# sha2017_rev1_0_0.net
KiCad netlist of a schematic drawn in EAGLE
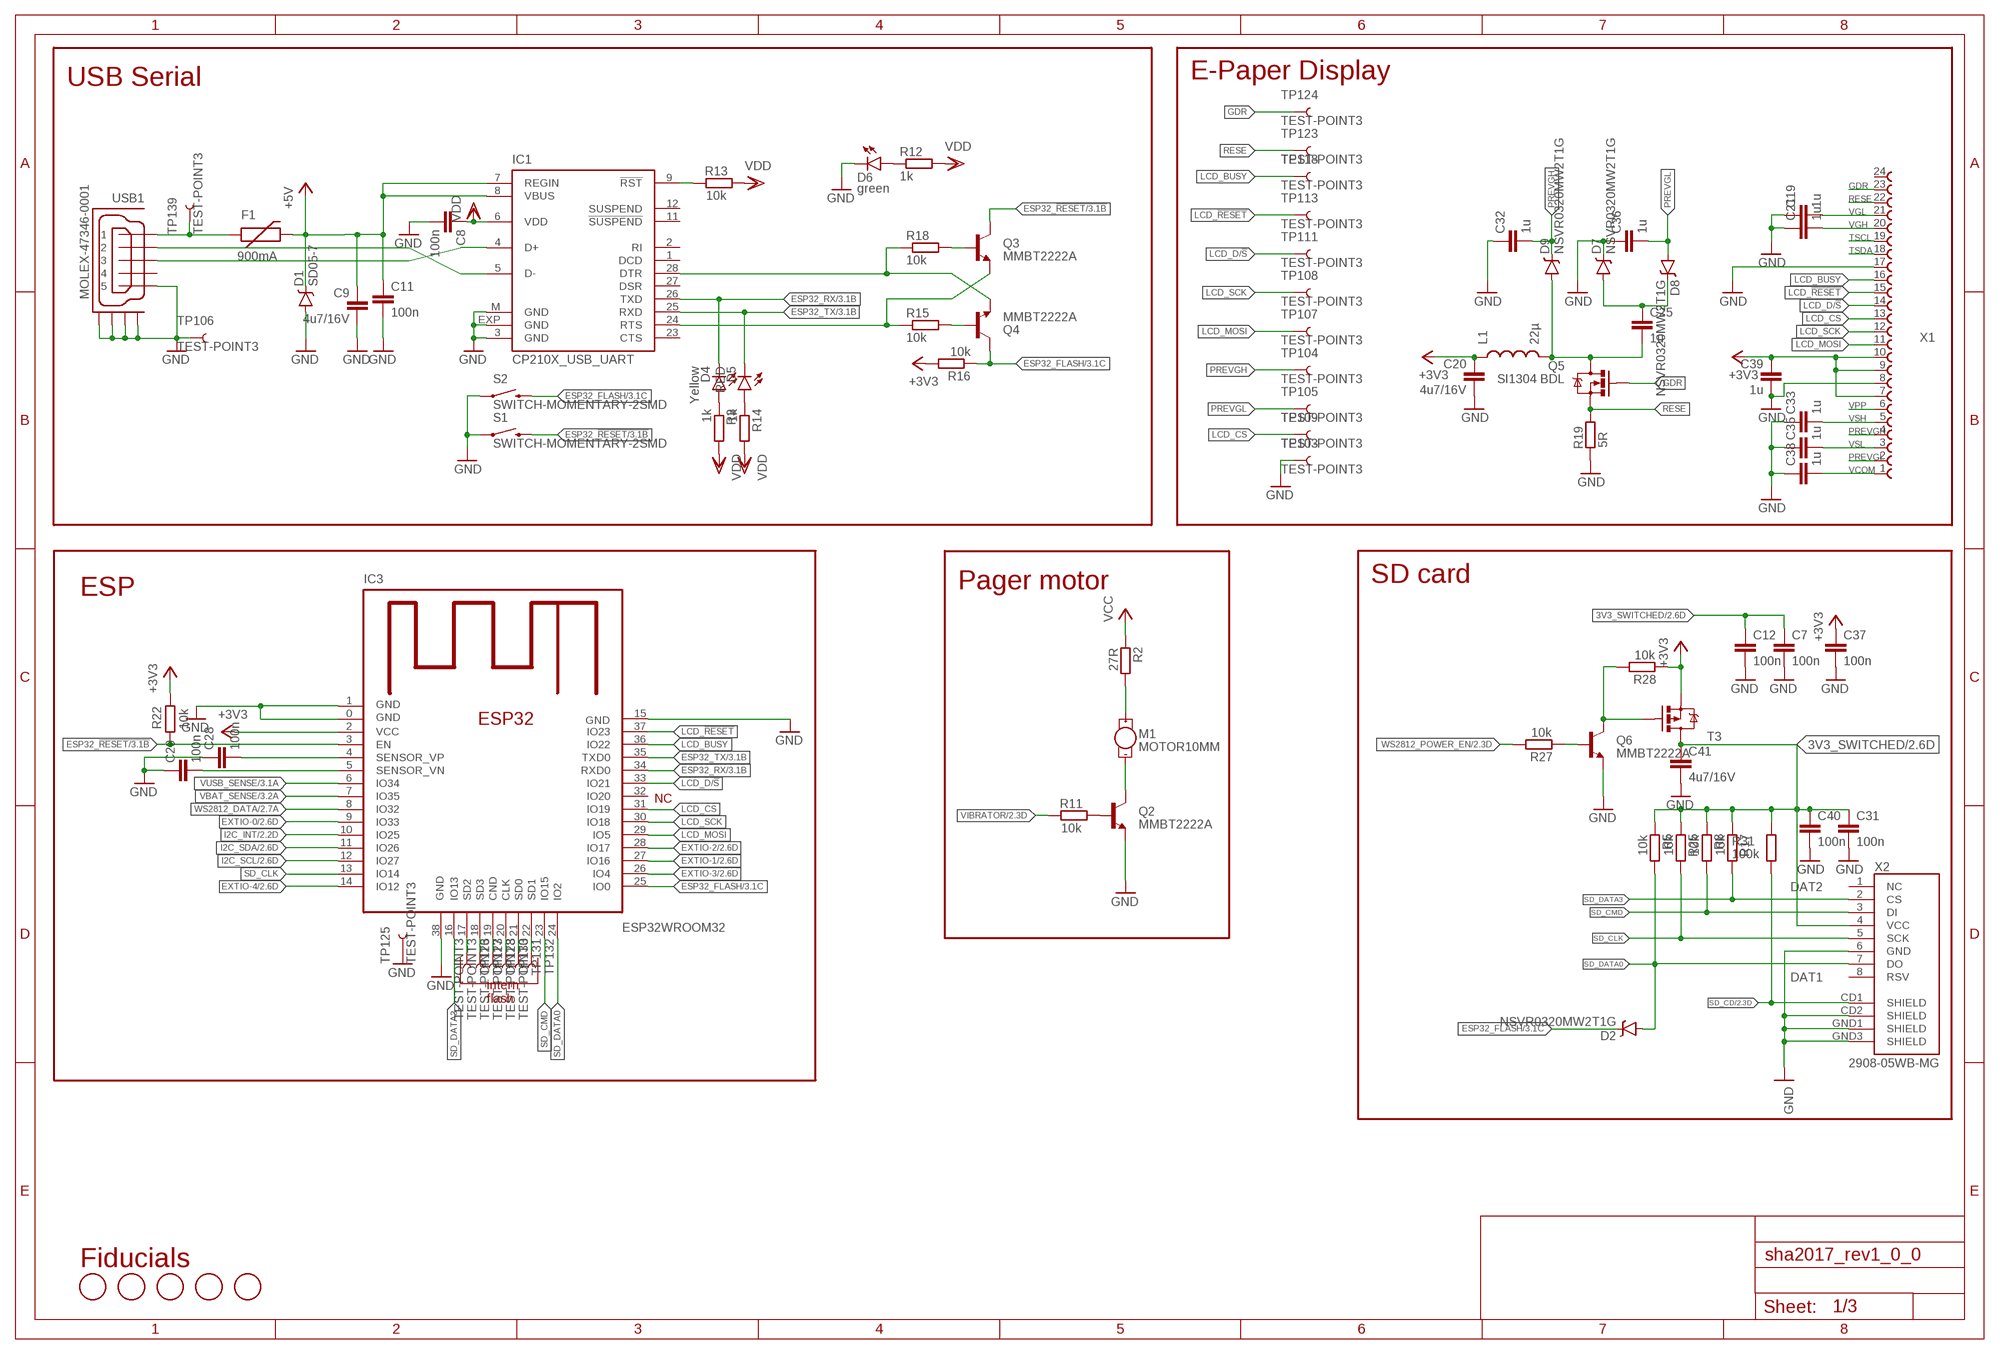
[diagram p0: schematic, sheet 1]
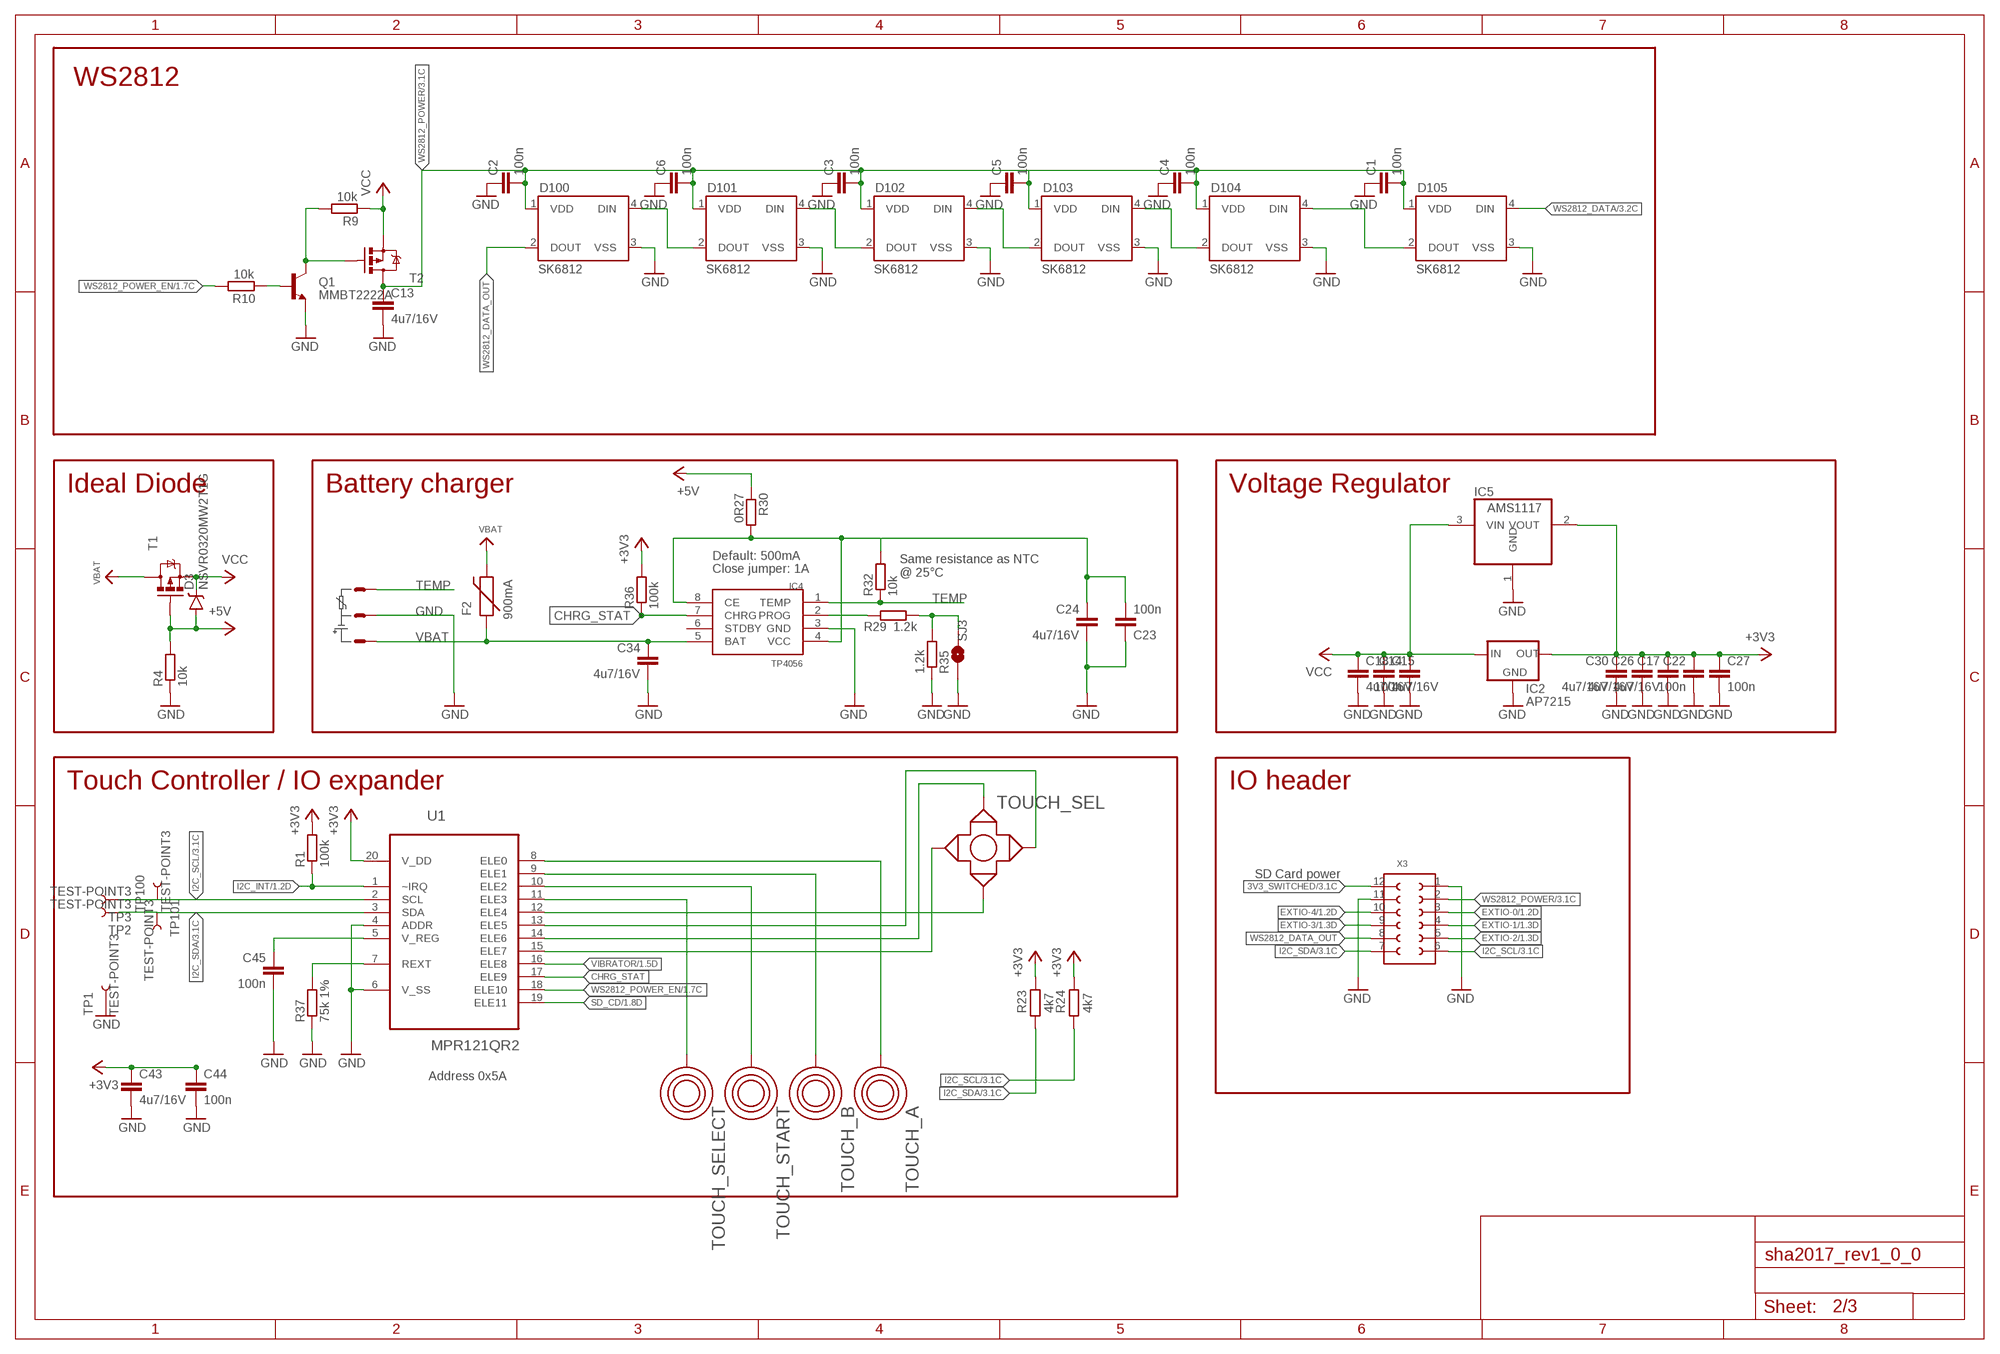
[diagram p1: schematic, sheet 2]
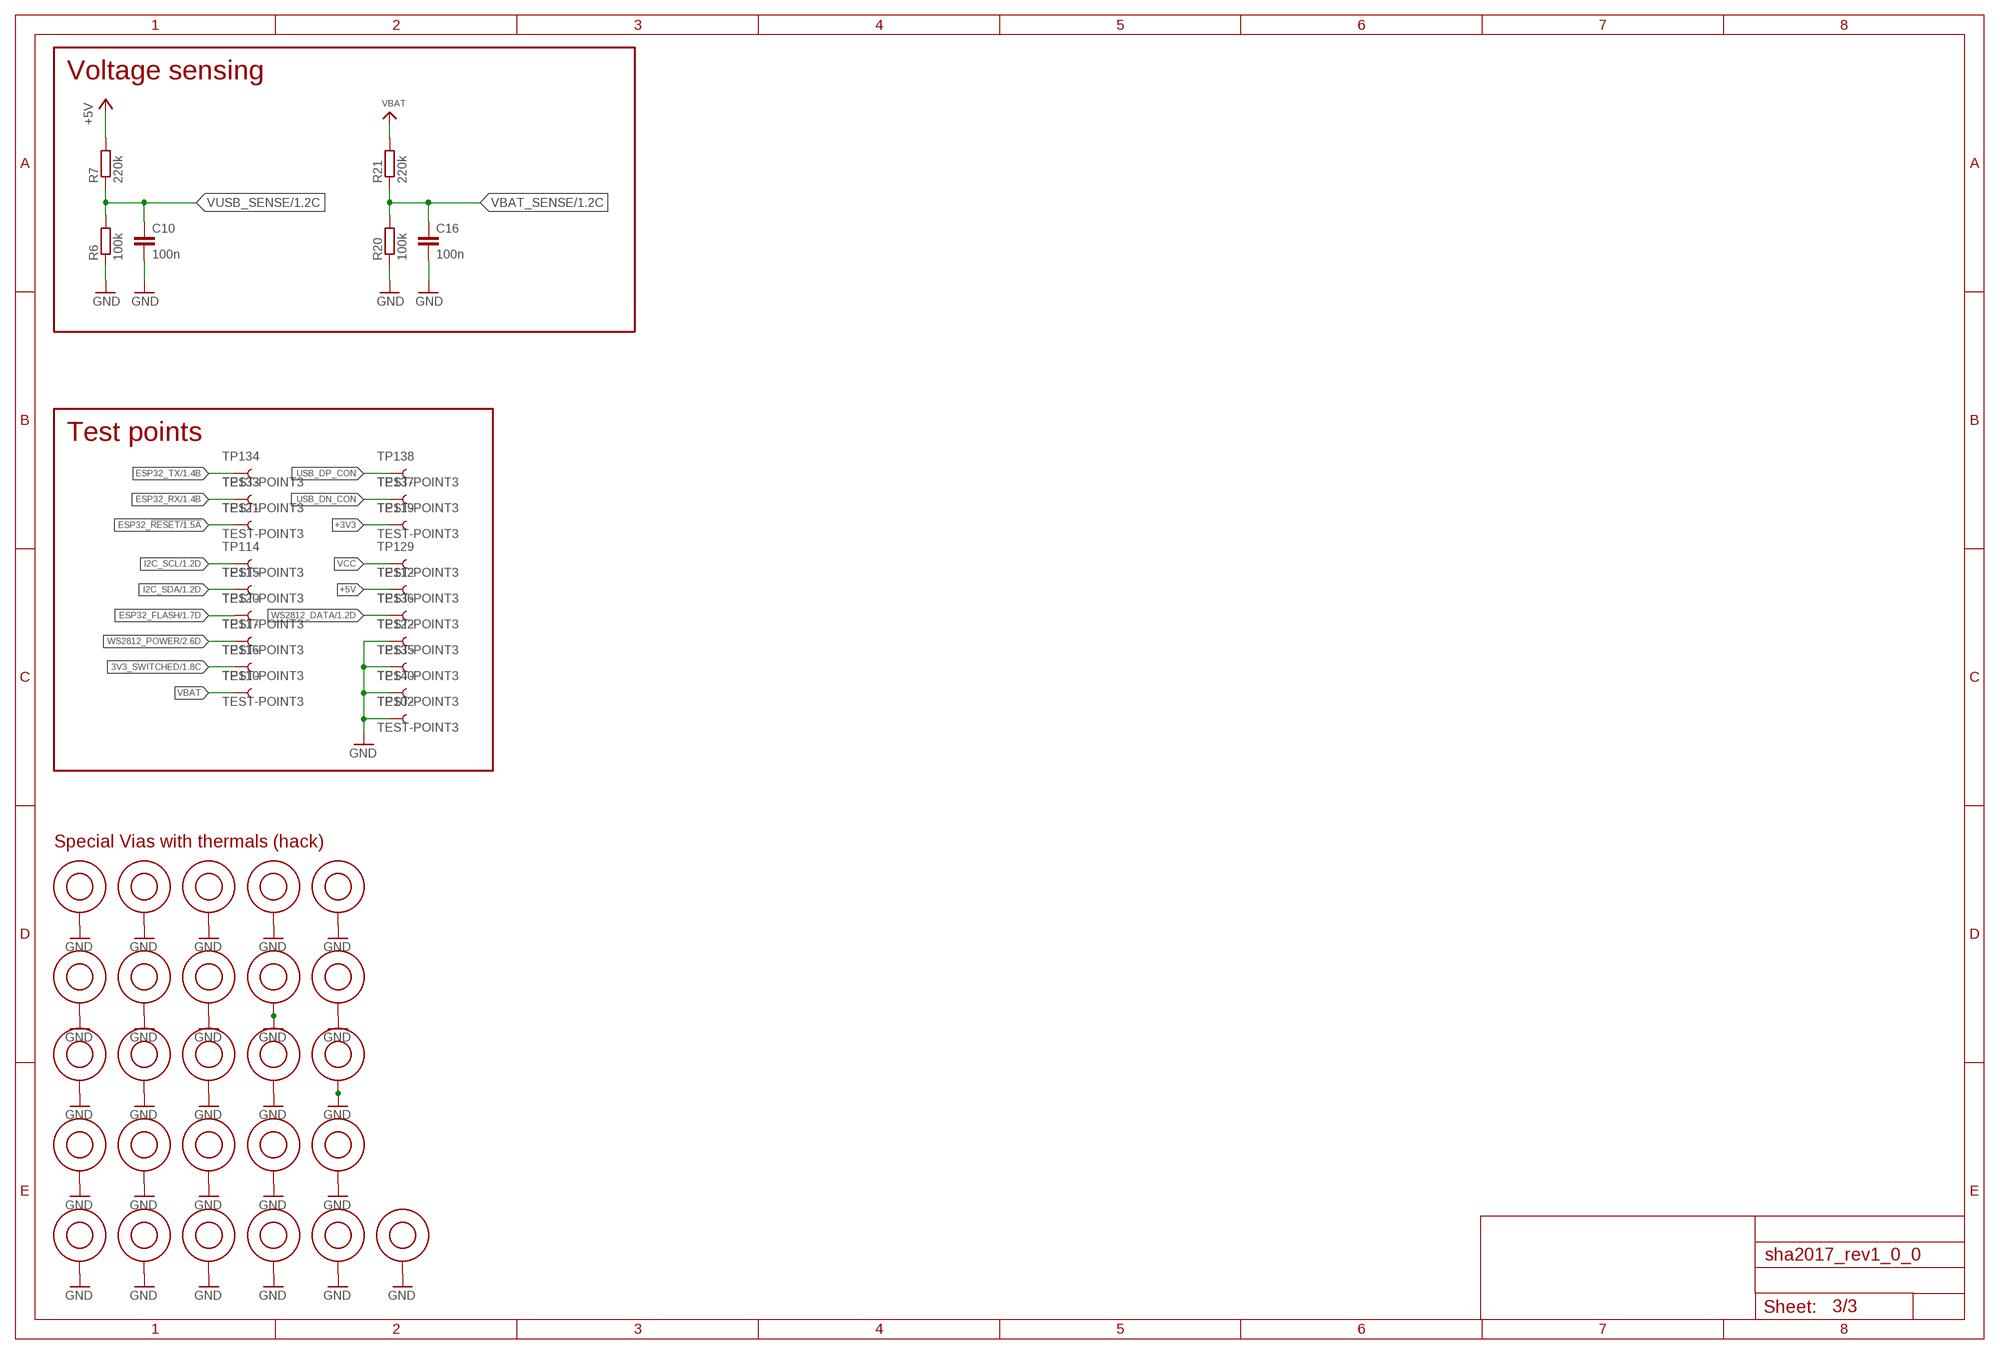
[diagram p2: schematic, sheet 3]

(export (version "E")
  (design (tool "Eeschema 10.0.6"))
  (components
    (comp (ref "C1")
      (value "100n")
      (footprint "eagle-import:C0603-DASHES")
      (fields (field (name "PARTNO") "GRM188R71H104KA93D"))
      (libsource (lib "eagle-import") (part "C0603-DASHES"))
    )
    (comp (ref "C2")
      (value "100n")
      (footprint "eagle-import:C0603-DASHES")
      (fields (field (name "PARTNO") "GRM188R71H104KA93D"))
      (libsource (lib "eagle-import") (part "C0603-DASHES"))
    )
    (comp (ref "C3")
      (value "100n")
      (footprint "eagle-import:C0603-DASHES")
      (fields (field (name "PARTNO") "GRM188R71H104KA93D"))
      (libsource (lib "eagle-import") (part "C0603-DASHES"))
    )
    (comp (ref "C4")
      (value "100n")
      (footprint "eagle-import:C0603-DASHES")
      (fields (field (name "PARTNO") "GRM188R71H104KA93D"))
      (libsource (lib "eagle-import") (part "C0603-DASHES"))
    )
    (comp (ref "C5")
      (value "100n")
      (footprint "eagle-import:C0603-DASHES")
      (fields (field (name "PARTNO") "GRM188R71H104KA93D"))
      (libsource (lib "eagle-import") (part "C0603-DASHES"))
    )
    (comp (ref "C6")
      (value "100n")
      (footprint "eagle-import:C0603-DASHES")
      (fields (field (name "PARTNO") "GRM188R71H104KA93D"))
      (libsource (lib "eagle-import") (part "C0603-DASHES"))
    )
    (comp (ref "C13")
      (value "4u7/16V")
      (footprint "eagle-import:C0805")
      (fields (field (name "PARTNO") "GRM21BR61C475KA88K"))
      (libsource (lib "eagle-import") (part "C-EUC0805"))
    )
    (comp (ref "C14")
      (value "100n")
      (footprint "eagle-import:C0603-DASHES")
      (fields (field (name "PARTNO") "GRM188R71H104KA93D"))
      (libsource (lib "eagle-import") (part "C0603-DASHES"))
    )
    (comp (ref "C15")
      (value "4u7/16V")
      (footprint "eagle-import:C0805")
      (fields (field (name "PARTNO") "GRM21BR61C475KA88K"))
      (libsource (lib "eagle-import") (part "C-EUC0805"))
    )
    (comp (ref "C17")
      (value "4u7/16V")
      (footprint "eagle-import:C0805")
      (fields (field (name "PARTNO") "GRM21BR61C475KA88K"))
      (libsource (lib "eagle-import") (part "C-EUC0805"))
    )
    (comp (ref "C18")
      (value "4u7/16V")
      (footprint "eagle-import:C0805")
      (fields (field (name "PARTNO") "GRM21BR61C475KA88K"))
      (libsource (lib "eagle-import") (part "C-EUC0805"))
    )
    (comp (ref "C22")
      (value "100n")
      (footprint "eagle-import:C0603-DASHES")
      (fields (field (name "PARTNO") "GRM188R71H104KA93D"))
      (libsource (lib "eagle-import") (part "C0603-DASHES"))
    )
    (comp (ref "C23")
      (value "100n")
      (footprint "eagle-import:C0603-DASHES")
      (fields (field (name "PARTNO") "GRM188R71H104KA93D"))
      (libsource (lib "eagle-import") (part "C0603-DASHES"))
    )
    (comp (ref "C24")
      (value "4u7/16V")
      (footprint "eagle-import:C0805")
      (fields (field (name "PARTNO") "GRM21BR61C475KA88K"))
      (libsource (lib "eagle-import") (part "C-EUC0805"))
    )
    (comp (ref "C26")
      (value "4u7/16V")
      (footprint "eagle-import:C0805")
      (fields (field (name "PARTNO") "GRM21BR61C475KA88K"))
      (libsource (lib "eagle-import") (part "C-EUC0805"))
    )
    (comp (ref "C27")
      (value "100n")
      (footprint "eagle-import:C0603-DASHES")
      (fields (field (name "PARTNO") "GRM188R71H104KA93D"))
      (libsource (lib "eagle-import") (part "C0603-DASHES"))
    )
    (comp (ref "C30")
      (value "4u7/16V")
      (footprint "eagle-import:C0805")
      (fields (field (name "PARTNO") "GRM21BR61C475KA88K"))
      (libsource (lib "eagle-import") (part "C-EUC0805"))
    )
    (comp (ref "C34")
      (value "4u7/16V")
      (footprint "eagle-import:C0805")
      (fields (field (name "PARTNO") "GRM21BR61C475KA88K"))
      (libsource (lib "eagle-import") (part "C-EUC0805"))
    )
    (comp (ref "C43")
      (value "4u7/16V")
      (footprint "eagle-import:C0805")
      (fields (field (name "PARTNO") "GRM21BR61C475KA88K"))
      (libsource (lib "eagle-import") (part "C-EUC0805"))
    )
    (comp (ref "C44")
      (value "100n")
      (footprint "eagle-import:C0603-DASHES")
      (fields (field (name "PARTNO") "GRM188R71H104KA93D"))
      (libsource (lib "eagle-import") (part "C0603-DASHES"))
    )
    (comp (ref "C45")
      (value "100n")
      (footprint "eagle-import:C0603-DASHES")
      (fields (field (name "PARTNO") "GRM188R71H104KA93D"))
      (libsource (lib "eagle-import") (part "C0603-DASHES"))
    )
    (comp (ref "D3")
      (value "NSVR0320MW2T1G")
      (footprint "eagle-import:SOD-323")
      (fields (field (name "PARTNO") "BAT20JFILM"))
      (libsource (lib "eagle-import") (part "BAT20JFILM"))
    )
    (comp (ref "D100")
      (value "SK6812")
      (footprint "eagle-import:WS2812B")
      (libsource (lib "eagle-import") (part "WS2812B"))
    )
    (comp (ref "D101")
      (value "SK6812")
      (footprint "eagle-import:WS2812B")
      (libsource (lib "eagle-import") (part "WS2812B"))
    )
    (comp (ref "D102")
      (value "SK6812")
      (footprint "eagle-import:WS2812B")
      (libsource (lib "eagle-import") (part "WS2812B"))
    )
    (comp (ref "D103")
      (value "SK6812")
      (footprint "eagle-import:WS2812B")
      (libsource (lib "eagle-import") (part "WS2812B"))
    )
    (comp (ref "D104")
      (value "SK6812")
      (footprint "eagle-import:WS2812B")
      (libsource (lib "eagle-import") (part "WS2812B"))
    )
    (comp (ref "D105")
      (value "SK6812")
      (footprint "eagle-import:WS2812B")
      (libsource (lib "eagle-import") (part "WS2812B"))
    )
    (comp (ref "F2")
      (value "900mA")
      (footprint "eagle-import:PTC-1206")
      (libsource (lib "eagle-import") (part "PTCSMD"))
    )
    (comp (ref "IC2")
      (value "AP7215")
      (footprint "eagle-import:SOT89")
      (fields (field (name "PARTNO") "AP7215-33YG-13"))
      (libsource (lib "eagle-import") (part "AP7215"))
    )
    (comp (ref "IC4")
      (value "TP4056")
      (footprint "eagle-import:SOP-8")
      (libsource (lib "eagle-import") (part "TP4056"))
    )
    (comp (ref "IC5")
      (value "AMS1117")
      (footprint "eagle-import:SOT223")
      (fields (field (name "MPN") "REG1117"))
      (libsource (lib "eagle-import") (part "REG1117"))
    )
    (comp (ref "Q1")
      (value "MMBT2222A")
      (footprint "eagle-import:SOT23-3")
      (fields (field (name "PARTNO") "BC817-25,215"))
      (libsource (lib "eagle-import") (part "TRANSISTOR_NPNMMBT2222A"))
    )
    (comp (ref "R1")
      (value "100k")
      (footprint "eagle-import:R0603-DASHES")
      (fields (field (name "PARTNO") "ERJ-3GEYJ104V"))
      (libsource (lib "eagle-import") (part "sha2017_rev0_1_0_dev_R0603-DASHES"))
    )
    (comp (ref "R4")
      (value "10k")
      (footprint "eagle-import:R0603-DASHES")
      (fields (field (name "PARTNO") "ERJ-3GEYJ103V"))
      (libsource (lib "eagle-import") (part "sha2017_rev0_1_0_dev_R0603-DASHES"))
    )
    (comp (ref "R9")
      (value "10k")
      (footprint "eagle-import:R0603-DASHES")
      (fields (field (name "PARTNO") "ERJ-3GEYJ103V"))
      (libsource (lib "eagle-import") (part "R0603-DASHES"))
    )
    (comp (ref "R10")
      (value "10k")
      (footprint "eagle-import:R0603-DASHES")
      (fields (field (name "PARTNO") "ERJ-3GEYJ103V"))
      (libsource (lib "eagle-import") (part "R0603-DASHES"))
    )
    (comp (ref "R23")
      (value "4k7")
      (footprint "eagle-import:R0603-DASHES")
      (fields (field (name "PARTNO") "ERJ-3GEYJ103V"))
      (libsource (lib "eagle-import") (part "sha2017_rev0_1_0_dev_R0603-DASHES"))
    )
    (comp (ref "R24")
      (value "4k7")
      (footprint "eagle-import:R0603-DASHES")
      (fields (field (name "PARTNO") "ERJ-3GEYJ103V"))
      (libsource (lib "eagle-import") (part "sha2017_rev0_1_0_dev_R0603-DASHES"))
    )
    (comp (ref "R29")
      (value "1.2k")
      (footprint "eagle-import:R0603-DASHES")
      (fields (field (name "PARTNO") "ERJ-3GEYJ222V"))
      (libsource (lib "eagle-import") (part "sha2017_rev0_1_0_dev_R0603-DASHES"))
    )
    (comp (ref "R30")
      (value "0R27")
      (footprint "eagle-import:R1206")
      (fields (field (name "PARTNO") "ERJ-3GEYJ154V"))
      (libsource (lib "eagle-import") (part "R-EU_R1206"))
    )
    (comp (ref "R32")
      (value "10k")
      (footprint "eagle-import:R0603-DASHES")
      (fields (field (name "PARTNO") "ERJ-3GEYJ154V"))
      (libsource (lib "eagle-import") (part "sha2017_rev0_1_0_dev_R0603-DASHES"))
    )
    (comp (ref "R35")
      (value "1.2k")
      (footprint "eagle-import:R0603-DASHES")
      (fields (field (name "PARTNO") "ERJ-3GEYJ222V"))
      (libsource (lib "eagle-import") (part "sha2017_rev0_1_0_dev_R0603-DASHES"))
    )
    (comp (ref "R36")
      (value "100k")
      (footprint "eagle-import:R0603-DASHES")
      (fields (field (name "PARTNO") "ERJ-3GEYJ104V"))
      (libsource (lib "eagle-import") (part "sha2017_rev0_1_0_dev_R0603-DASHES"))
    )
    (comp (ref "R37")
      (value "75k 1%")
      (footprint "eagle-import:R0603-DASHES")
      (fields (field (name "PARTNO") "ERJ-3GEYJ104V"))
      (libsource (lib "eagle-import") (part "sha2017_rev0_1_0_dev_R0603-DASHES"))
    )
    (comp (ref "SJ3")
      (value "JUMPER-PAD-2-NOYES_SILK")
      (footprint "eagle-import:PAD-JUMPER-2-NO_YES_SILK")
      (fields (field (name "PARTNO") "NAP"))
      (libsource (lib "eagle-import") (part "JUMPER-PAD-2-NOYES_SILK"))
    )
    (comp (ref "T1")
      (value "MOSFET-PCHANNEL")
      (footprint "eagle-import:SOT23-3")
      (libsource (lib "eagle-import") (part "MOSFET-PCHANNEL"))
    )
    (comp (ref "T2")
      (value "MOSFET-PCHANNEL")
      (footprint "eagle-import:SOT23-3")
      (libsource (lib "eagle-import") (part "MOSFET-PCHANNEL"))
    )
    (comp (ref "TOUCH_A")
      (value "TOUCHROUND")
      (footprint "eagle-import:TOUCH_BUTTON")
      (fields (field (name "PARTNO") "NAP"))
      (libsource (lib "eagle-import") (part "TOUCHROUND"))
    )
    (comp (ref "TOUCH_B")
      (value "TOUCHROUND")
      (footprint "eagle-import:TOUCH_BUTTON")
      (fields (field (name "PARTNO") "NAP"))
      (libsource (lib "eagle-import") (part "TOUCHROUND"))
    )
    (comp (ref "TOUCH_SEL")
      (value "TOUCH_CROSS")
      (footprint "eagle-import:TOUCH_CROSS")
      (fields (field (name "PARTNO") "NAP"))
      (libsource (lib "eagle-import") (part "TOUCH_CROSS"))
    )
    (comp (ref "TOUCH_SELECT")
      (value "TOUCHSELECT")
      (footprint "eagle-import:TOUCH_SELECT")
      (libsource (lib "eagle-import") (part "TOUCHSELECT"))
    )
    (comp (ref "TOUCH_START")
      (value "TOUCHSELECT")
      (footprint "eagle-import:TOUCH_SELECT")
      (libsource (lib "eagle-import") (part "TOUCHSELECT"))
    )
    (comp (ref "TP1")
      (value "TEST-POINT3")
      (footprint "eagle-import:PAD.03X.03")
      (fields (field (name "PARTNO") "NAP"))
      (libsource (lib "eagle-import") (part "TEST-POINT3"))
    )
    (comp (ref "TP2")
      (value "TEST-POINT3")
      (footprint "eagle-import:PAD.03X.03")
      (fields (field (name "PARTNO") "NAP"))
      (libsource (lib "eagle-import") (part "TEST-POINT3"))
    )
    (comp (ref "TP3")
      (value "TEST-POINT3")
      (footprint "eagle-import:PAD.03X.03")
      (fields (field (name "PARTNO") "NAP"))
      (libsource (lib "eagle-import") (part "TEST-POINT3"))
    )
    (comp (ref "TP100")
      (value "TEST-POINT3")
      (footprint "eagle-import:PAD.03X.03")
      (fields (field (name "PARTNO") "NAP"))
      (libsource (lib "eagle-import") (part "TEST-POINT3"))
    )
    (comp (ref "TP101")
      (value "TEST-POINT3")
      (footprint "eagle-import:PAD.03X.03")
      (fields (field (name "PARTNO") "NAP"))
      (libsource (lib "eagle-import") (part "TEST-POINT3"))
    )
    (comp (ref "U1")
      (value "MPR121QR2")
      (footprint "eagle-import:QFN40P300X300X60-20N")
      (libsource (lib "eagle-import") (part "MPR121QR2"))
    )
    (comp (ref "X3")
      (value "610X12243021")
      (footprint "eagle-import:610X12243021")
      (fields (field (name "PARTNO") "517-153208-2020-TB"))
      (libsource (lib "eagle-import") (part "610X12243021"))
    )
    (comp (ref "X4")
      (value "JST-PH3")
      (footprint "eagle-import:JST-PH3")
      (libsource (lib "eagle-import") (part "JST-PH3"))
    )
    (comp (ref "$$U$1")
      (value "VIA")
      (footprint "eagle-import:VIA")
      (fields (field (name "PARTNO") "NAP"))
      (libsource (lib "eagle-import") (part "VIA"))
    )
    (comp (ref "$$U$2")
      (value "VIA")
      (footprint "eagle-import:VIA")
      (fields (field (name "PARTNO") "NAP"))
      (libsource (lib "eagle-import") (part "VIA"))
    )
    (comp (ref "$$U$3")
      (value "VIA")
      (footprint "eagle-import:VIA")
      (fields (field (name "PARTNO") "NAP"))
      (libsource (lib "eagle-import") (part "VIA"))
    )
    (comp (ref "$$U$4")
      (value "VIA")
      (footprint "eagle-import:VIA")
      (fields (field (name "PARTNO") "NAP"))
      (libsource (lib "eagle-import") (part "VIA"))
    )
    (comp (ref "$$U$5")
      (value "VIA")
      (footprint "eagle-import:VIA")
      (fields (field (name "PARTNO") "NAP"))
      (libsource (lib "eagle-import") (part "VIA"))
    )
    (comp (ref "$$U$6")
      (value "VIA")
      (footprint "eagle-import:VIA")
      (fields (field (name "PARTNO") "NAP"))
      (libsource (lib "eagle-import") (part "VIA"))
    )
    (comp (ref "$$U$7")
      (value "VIA")
      (footprint "eagle-import:VIA")
      (fields (field (name "PARTNO") "NAP"))
      (libsource (lib "eagle-import") (part "VIA"))
    )
    (comp (ref "$$U$8")
      (value "VIA")
      (footprint "eagle-import:VIA")
      (fields (field (name "PARTNO") "NAP"))
      (libsource (lib "eagle-import") (part "VIA"))
    )
    (comp (ref "$$U$9")
      (value "VIA")
      (footprint "eagle-import:VIA")
      (fields (field (name "PARTNO") "NAP"))
      (libsource (lib "eagle-import") (part "VIA"))
    )
    (comp (ref "C10")
      (value "100n")
      (footprint "eagle-import:C0603-DASHES")
      (fields (field (name "PARTNO") "GRM188R71H104KA93D"))
      (libsource (lib "eagle-import") (part "C0603-DASHES"))
    )
    (comp (ref "C16")
      (value "100n")
      (footprint "eagle-import:C0603-DASHES")
      (fields (field (name "PARTNO") "GRM188R71H104KA93D"))
      (libsource (lib "eagle-import") (part "C0603-DASHES"))
    )
    (comp (ref "R6")
      (value "100k")
      (footprint "eagle-import:R0603-DASHES")
      (fields (field (name "PARTNO") "ERJ-3GEYJ104V"))
      (libsource (lib "eagle-import") (part "sha2017_rev0_1_0_dev_R0603-DASHES"))
    )
    (comp (ref "R7")
      (value "220k")
      (footprint "eagle-import:R0603-DASHES")
      (fields (field (name "PARTNO") "ERJ-3GEYJ224V"))
      (libsource (lib "eagle-import") (part "sha2017_rev0_1_0_dev_R0603-DASHES"))
    )
    (comp (ref "R20")
      (value "100k")
      (footprint "eagle-import:R0603-DASHES")
      (fields (field (name "PARTNO") "ERJ-3GEYJ104V"))
      (libsource (lib "eagle-import") (part "sha2017_rev0_1_0_dev_R0603-DASHES"))
    )
    (comp (ref "R21")
      (value "220k")
      (footprint "eagle-import:R0603-DASHES")
      (fields (field (name "PARTNO") "ERJ-3GEYJ224V"))
      (libsource (lib "eagle-import") (part "sha2017_rev0_1_0_dev_R0603-DASHES"))
    )
    (comp (ref "TP102")
      (value "TEST-POINT3")
      (footprint "eagle-import:PAD.03X.03")
      (fields (field (name "PARTNO") "NAP"))
      (libsource (lib "eagle-import") (part "TEST-POINT3"))
    )
    (comp (ref "TP110")
      (value "TEST-POINT3")
      (footprint "eagle-import:PAD.03X.03")
      (fields (field (name "PARTNO") "NAP"))
      (libsource (lib "eagle-import") (part "TEST-POINT3"))
    )
    (comp (ref "TP112")
      (value "TEST-POINT3")
      (footprint "eagle-import:PAD.03X.03")
      (fields (field (name "PARTNO") "NAP"))
      (libsource (lib "eagle-import") (part "TEST-POINT3"))
    )
    (comp (ref "TP114")
      (value "TEST-POINT3")
      (footprint "eagle-import:PAD.03X.03")
      (fields (field (name "PARTNO") "NAP"))
      (libsource (lib "eagle-import") (part "TEST-POINT3"))
    )
    (comp (ref "TP115")
      (value "TEST-POINT3")
      (footprint "eagle-import:PAD.03X.03")
      (fields (field (name "PARTNO") "NAP"))
      (libsource (lib "eagle-import") (part "TEST-POINT3"))
    )
    (comp (ref "TP116")
      (value "TEST-POINT3")
      (footprint "eagle-import:PAD.03X.03")
      (fields (field (name "PARTNO") "NAP"))
      (libsource (lib "eagle-import") (part "TEST-POINT3"))
    )
    (comp (ref "TP117")
      (value "TEST-POINT3")
      (footprint "eagle-import:PAD.03X.03")
      (fields (field (name "PARTNO") "NAP"))
      (libsource (lib "eagle-import") (part "TEST-POINT3"))
    )
    (comp (ref "TP119")
      (value "TEST-POINT3")
      (footprint "eagle-import:PAD.03X.03")
      (fields (field (name "PARTNO") "NAP"))
      (libsource (lib "eagle-import") (part "TEST-POINT3"))
    )
    (comp (ref "TP120")
      (value "TEST-POINT3")
      (footprint "eagle-import:PAD.03X.03")
      (fields (field (name "PARTNO") "NAP"))
      (libsource (lib "eagle-import") (part "TEST-POINT3"))
    )
    (comp (ref "TP121")
      (value "TEST-POINT3")
      (footprint "eagle-import:PAD.03X.03")
      (fields (field (name "PARTNO") "NAP"))
      (libsource (lib "eagle-import") (part "TEST-POINT3"))
    )
    (comp (ref "TP122")
      (value "TEST-POINT3")
      (footprint "eagle-import:PAD.03X.03")
      (fields (field (name "PARTNO") "NAP"))
      (libsource (lib "eagle-import") (part "TEST-POINT3"))
    )
    (comp (ref "TP129")
      (value "TEST-POINT3")
      (footprint "eagle-import:PAD.03X.03")
      (fields (field (name "PARTNO") "NAP"))
      (libsource (lib "eagle-import") (part "TEST-POINT3"))
    )
    (comp (ref "TP133")
      (value "TEST-POINT3")
      (footprint "eagle-import:PAD.03X.03")
      (fields (field (name "PARTNO") "NAP"))
      (libsource (lib "eagle-import") (part "TEST-POINT3"))
    )
    (comp (ref "TP134")
      (value "TEST-POINT3")
      (footprint "eagle-import:PAD.03X.03")
      (fields (field (name "PARTNO") "NAP"))
      (libsource (lib "eagle-import") (part "TEST-POINT3"))
    )
    (comp (ref "TP135")
      (value "TEST-POINT3")
      (footprint "eagle-import:PAD.03X.03")
      (fields (field (name "PARTNO") "NAP"))
      (libsource (lib "eagle-import") (part "TEST-POINT3"))
    )
    (comp (ref "TP136")
      (value "TEST-POINT3")
      (footprint "eagle-import:PAD.03X.03")
      (fields (field (name "PARTNO") "NAP"))
      (libsource (lib "eagle-import") (part "TEST-POINT3"))
    )
    (comp (ref "TP137")
      (value "TEST-POINT3")
      (footprint "eagle-import:PAD.03X.03")
      (fields (field (name "PARTNO") "NAP"))
      (libsource (lib "eagle-import") (part "TEST-POINT3"))
    )
    (comp (ref "TP138")
      (value "TEST-POINT3")
      (footprint "eagle-import:PAD.03X.03")
      (fields (field (name "PARTNO") "NAP"))
      (libsource (lib "eagle-import") (part "TEST-POINT3"))
    )
    (comp (ref "TP140")
      (value "TEST-POINT3")
      (footprint "eagle-import:PAD.03X.03")
      (fields (field (name "PARTNO") "NAP"))
      (libsource (lib "eagle-import") (part "TEST-POINT3"))
    )
    (comp (ref "U$2")
      (value "VIA")
      (footprint "eagle-import:VIA")
      (fields (field (name "PARTNO") "NAP"))
      (libsource (lib "eagle-import") (part "VIA"))
    )
    (comp (ref "U$3")
      (value "VIA")
      (footprint "eagle-import:VIA")
      (fields (field (name "PARTNO") "NAP"))
      (libsource (lib "eagle-import") (part "VIA"))
    )
    (comp (ref "U$4")
      (value "VIA")
      (footprint "eagle-import:VIA")
      (fields (field (name "PARTNO") "NAP"))
      (libsource (lib "eagle-import") (part "VIA"))
    )
    (comp (ref "U$5")
      (value "VIA")
      (footprint "eagle-import:VIA")
      (fields (field (name "PARTNO") "NAP"))
      (libsource (lib "eagle-import") (part "VIA"))
    )
    (comp (ref "U$6")
      (value "VIA")
      (footprint "eagle-import:VIA")
      (fields (field (name "PARTNO") "NAP"))
      (libsource (lib "eagle-import") (part "VIA"))
    )
    (comp (ref "U$10")
      (value "VIA")
      (footprint "eagle-import:VIA")
      (fields (field (name "PARTNO") "NAP"))
      (libsource (lib "eagle-import") (part "VIA"))
    )
    (comp (ref "U$11")
      (value "VIA")
      (footprint "eagle-import:VIA")
      (fields (field (name "PARTNO") "NAP"))
      (libsource (lib "eagle-import") (part "VIA"))
    )
    (comp (ref "U$12")
      (value "VIA")
      (footprint "eagle-import:VIA")
      (fields (field (name "PARTNO") "NAP"))
      (libsource (lib "eagle-import") (part "VIA"))
    )
    (comp (ref "U$13")
      (value "VIA")
      (footprint "eagle-import:VIA")
      (fields (field (name "PARTNO") "NAP"))
      (libsource (lib "eagle-import") (part "VIA"))
    )
    (comp (ref "U$14")
      (value "VIA")
      (footprint "eagle-import:VIA")
      (fields (field (name "PARTNO") "NAP"))
      (libsource (lib "eagle-import") (part "VIA"))
    )
    (comp (ref "U$15")
      (value "VIA")
      (footprint "eagle-import:VIA")
      (fields (field (name "PARTNO") "NAP"))
      (libsource (lib "eagle-import") (part "VIA"))
    )
    (comp (ref "U$16")
      (value "VIA")
      (footprint "eagle-import:VIA")
      (fields (field (name "PARTNO") "NAP"))
      (libsource (lib "eagle-import") (part "VIA"))
    )
    (comp (ref "U$17")
      (value "VIA")
      (footprint "eagle-import:VIA")
      (fields (field (name "PARTNO") "NAP"))
      (libsource (lib "eagle-import") (part "VIA"))
    )
    (comp (ref "U$18")
      (value "VIA")
      (footprint "eagle-import:VIA")
      (fields (field (name "PARTNO") "NAP"))
      (libsource (lib "eagle-import") (part "VIA"))
    )
    (comp (ref "U$19")
      (value "VIA")
      (footprint "eagle-import:VIA")
      (fields (field (name "PARTNO") "NAP"))
      (libsource (lib "eagle-import") (part "VIA"))
    )
    (comp (ref "U$20")
      (value "VIA")
      (footprint "eagle-import:VIA")
      (fields (field (name "PARTNO") "NAP"))
      (libsource (lib "eagle-import") (part "VIA"))
    )
    (comp (ref "U$21")
      (value "VIA")
      (footprint "eagle-import:VIA")
      (fields (field (name "PARTNO") "NAP"))
      (libsource (lib "eagle-import") (part "VIA"))
    )
    (comp (ref "U$22")
      (value "VIA")
      (footprint "eagle-import:VIA")
      (fields (field (name "PARTNO") "NAP"))
      (libsource (lib "eagle-import") (part "VIA"))
    )
    (comp (ref "U$23")
      (value "VIA")
      (footprint "eagle-import:VIA")
      (fields (field (name "PARTNO") "NAP"))
      (libsource (lib "eagle-import") (part "VIA"))
    )
    (comp (ref "C7")
      (value "100n")
      (footprint "eagle-import:C0603-DASHES")
      (fields (field (name "PARTNO") "GRM188R71H104KA93D"))
      (libsource (lib "eagle-import") (part "C0603-DASHES"))
    )
    (comp (ref "C8")
      (value "100n")
      (footprint "eagle-import:C0603-DASHES")
      (fields (field (name "PARTNO") "GRM188R71H104KA93D"))
      (libsource (lib "eagle-import") (part "C0603-DASHES"))
    )
    (comp (ref "C9")
      (value "4u7/16V")
      (footprint "eagle-import:C0805")
      (fields (field (name "PARTNO") "GRM21BR61C475KA88K"))
      (libsource (lib "eagle-import") (part "C-EUC0805"))
    )
    (comp (ref "C11")
      (value "100n")
      (footprint "eagle-import:C0603-DASHES")
      (fields (field (name "PARTNO") "GRM188R71H104KA93D"))
      (libsource (lib "eagle-import") (part "C0603-DASHES"))
    )
    (comp (ref "C12")
      (value "100n")
      (footprint "eagle-import:C0603-DASHES")
      (fields (field (name "PARTNO") "GRM188R71H104KA93D"))
      (libsource (lib "eagle-import") (part "C0603-DASHES"))
    )
    (comp (ref "C19")
      (value "1u")
      (footprint "eagle-import:C0603-DASHES")
      (fields (field (name "PARTNO") "GRM188R61E105KA12D"))
      (libsource (lib "eagle-import") (part "C0603-DASHES"))
    )
    (comp (ref "C20")
      (value "4u7/16V")
      (footprint "eagle-import:C0805")
      (fields (field (name "PARTNO") "GRM21BR61C475KA88K"))
      (libsource (lib "eagle-import") (part "C-EUC0805"))
    )
    (comp (ref "C21")
      (value "1u")
      (footprint "eagle-import:C0603-DASHES")
      (fields (field (name "PARTNO") "GRM188R61E105KA12D"))
      (libsource (lib "eagle-import") (part "C0603-DASHES"))
    )
    (comp (ref "C25")
      (value "1u")
      (footprint "eagle-import:C0603-DASHES")
      (fields (field (name "PARTNO") "GRM188R61E105KA12D"))
      (libsource (lib "eagle-import") (part "C0603-DASHES"))
    )
    (comp (ref "C28")
      (value "100n")
      (footprint "eagle-import:C0603-DASHES")
      (fields (field (name "PARTNO") "GRM188R71H104KA93D"))
      (libsource (lib "eagle-import") (part "C0603-DASHES"))
    )
    (comp (ref "C29")
      (value "100n")
      (footprint "eagle-import:C0603-DASHES")
      (fields (field (name "PARTNO") "GRM188R71H104KA93D"))
      (libsource (lib "eagle-import") (part "C0603-DASHES"))
    )
    (comp (ref "C31")
      (value "100n")
      (footprint "eagle-import:C0603-DASHES")
      (fields (field (name "PARTNO") "GRM188R71H104KA93D"))
      (libsource (lib "eagle-import") (part "C0603-DASHES"))
    )
    (comp (ref "C32")
      (value "1u")
      (footprint "eagle-import:C0603-DASHES")
      (fields (field (name "PARTNO") "GRM188R61E105KA12D"))
      (libsource (lib "eagle-import") (part "C0603-DASHES"))
    )
    (comp (ref "C33")
      (value "1u")
      (footprint "eagle-import:C0603-DASHES")
      (fields (field (name "PARTNO") "GRM188R61E105KA12D"))
      (libsource (lib "eagle-import") (part "C0603-DASHES"))
    )
    (comp (ref "C35")
      (value "1u")
      (footprint "eagle-import:C0603-DASHES")
      (fields (field (name "PARTNO") "GRM188R61E105KA12D"))
      (libsource (lib "eagle-import") (part "C0603-DASHES"))
    )
    (comp (ref "C36")
      (value "1u")
      (footprint "eagle-import:C0603-DASHES")
      (fields (field (name "PARTNO") "GRM188R61E105KA12D"))
      (libsource (lib "eagle-import") (part "C0603-DASHES"))
    )
    (comp (ref "C37")
      (value "100n")
      (footprint "eagle-import:C0603-DASHES")
      (fields (field (name "PARTNO") "GRM188R71H104KA93D"))
      (libsource (lib "eagle-import") (part "C0603-DASHES"))
    )
    (comp (ref "C38")
      (value "1u")
      (footprint "eagle-import:C0603-DASHES")
      (fields (field (name "PARTNO") "GRM188R61E105KA12D"))
      (libsource (lib "eagle-import") (part "C0603-DASHES"))
    )
    (comp (ref "C39")
      (value "1u")
      (footprint "eagle-import:C0603-DASHES")
      (fields (field (name "PARTNO") "GRM188R61E105KA12D"))
      (libsource (lib "eagle-import") (part "C0603-DASHES"))
    )
    (comp (ref "C40")
      (value "100n")
      (footprint "eagle-import:C0603-DASHES")
      (fields (field (name "PARTNO") "GRM188R71H104KA93D"))
      (libsource (lib "eagle-import") (part "C0603-DASHES"))
    )
    (comp (ref "C41")
      (value "4u7/16V")
      (footprint "eagle-import:C0805")
      (fields (field (name "PARTNO") "GRM21BR61C475KA88K"))
      (libsource (lib "eagle-import") (part "C-EUC0805"))
    )
    (comp (ref "D1")
      (value "SD05-7")
      (footprint "eagle-import:SOD-323")
      (libsource (lib "eagle-import") (part "DIODE-SCHOTTKY-PMEG4005EJ"))
    )
    (comp (ref "D2")
      (value "NSVR0320MW2T1G")
      (footprint "eagle-import:SOD-323")
      (fields (field (name "PARTNO") "BAT20JFILM"))
      (libsource (lib "eagle-import") (part "BAT20JFILM"))
    )
    (comp (ref "D4")
      (value "Yellow")
      (footprint "eagle-import:LED-0603")
      (libsource (lib "eagle-import") (part "LED0603"))
    )
    (comp (ref "D5")
      (value "RED")
      (footprint "eagle-import:LED-0603")
      (libsource (lib "eagle-import") (part "LED0603"))
    )
    (comp (ref "D6")
      (value "green")
      (footprint "eagle-import:LED-0603")
      (libsource (lib "eagle-import") (part "LED0603"))
    )
    (comp (ref "D7")
      (value "NSVR0320MW2T1G")
      (footprint "eagle-import:SOD-323")
      (fields (field (name "PARTNO") "BAT20JFILM"))
      (libsource (lib "eagle-import") (part "BAT20JFILM"))
    )
    (comp (ref "D8")
      (value "NSVR0320MW2T1G")
      (footprint "eagle-import:SOD-323")
      (fields (field (name "PARTNO") "BAT20JFILM"))
      (libsource (lib "eagle-import") (part "BAT20JFILM"))
    )
    (comp (ref "D9")
      (value "NSVR0320MW2T1G")
      (footprint "eagle-import:SOD-323")
      (fields (field (name "PARTNO") "BAT20JFILM"))
      (libsource (lib "eagle-import") (part "BAT20JFILM"))
    )
    (comp (ref "F1")
      (value "900mA")
      (footprint "eagle-import:PTC-1206")
      (libsource (lib "eagle-import") (part "PTCSMD"))
    )
    (comp (ref "FD1")
      (value "FIDUCIAL")
      (footprint "eagle-import:FIDUCIAL_1MM")
      (fields (field (name "PARTNO") "NAP"))
      (libsource (lib "eagle-import") (part "FIDUCIAL"))
    )
    (comp (ref "FD2")
      (value "FIDUCIAL")
      (footprint "eagle-import:FIDUCIAL_1MM")
      (fields (field (name "PARTNO") "NAP"))
      (libsource (lib "eagle-import") (part "FIDUCIAL"))
    )
    (comp (ref "FD3")
      (value "FIDUCIAL")
      (footprint "eagle-import:FIDUCIAL_1MM")
      (fields (field (name "PARTNO") "NAP"))
      (libsource (lib "eagle-import") (part "FIDUCIAL"))
    )
    (comp (ref "FD4")
      (value "FIDUCIAL")
      (footprint "eagle-import:FIDUCIAL_1MM")
      (fields (field (name "PARTNO") "NAP"))
      (libsource (lib "eagle-import") (part "FIDUCIAL"))
    )
    (comp (ref "FD5")
      (value "FIDUCIAL")
      (footprint "eagle-import:FIDUCIAL_1MM")
      (fields (field (name "PARTNO") "NAP"))
      (libsource (lib "eagle-import") (part "FIDUCIAL"))
    )
    (comp (ref "IC1")
      (value "CP210X_USB_UART")
      (footprint "eagle-import:MLP28")
      (fields (field (name "PARTNO") "CP2102-GMR"))
      (libsource (lib "eagle-import") (part "CP210X_USB_UART"))
    )
    (comp (ref "IC3")
      (value "ESP32WROOM32")
      (footprint "eagle-import:ESP32MOD")
      (libsource (lib "eagle-import") (part "ESP32WROOM32"))
    )
    (comp (ref "L1")
      (value "22µ")
      (footprint "eagle-import:1210")
      (fields (field (name "PARTNO") "NLCV32T-220K-EF"))
      (libsource (lib "eagle-import") (part "INDUCTOR1210"))
    )
    (comp (ref "M1")
      (value "MOTOR10MM")
      (footprint "eagle-import:VIBE-MOTOR-10MM")
      (libsource (lib "eagle-import") (part "MOTOR10MM"))
    )
    (comp (ref "Q2")
      (value "MMBT2222A")
      (footprint "eagle-import:SOT23-3")
      (fields (field (name "PARTNO") "BC817-25,215"))
      (libsource (lib "eagle-import") (part "TRANSISTOR_NPNMMBT2222A"))
    )
    (comp (ref "Q3")
      (value "MMBT2222A")
      (footprint "eagle-import:SOT23-3")
      (fields (field (name "PARTNO") "BC817-25,215"))
      (libsource (lib "eagle-import") (part "TRANSISTOR_NPNMMBT2222A"))
    )
    (comp (ref "Q4")
      (value "MMBT2222A")
      (footprint "eagle-import:SOT23-3")
      (fields (field (name "PARTNO") "BC817-25,215"))
      (libsource (lib "eagle-import") (part "TRANSISTOR_NPNMMBT2222A"))
    )
    (comp (ref "Q5")
      (value "SI1304 BDL")
      (footprint "eagle-import:SOT323")
      (fields (field (name "PARTNO") "SI1308EDL-T1-GE3"))
      (libsource (lib "eagle-import") (part "MOSFET-NCHANNEL2N7002PW"))
    )
    (comp (ref "Q6")
      (value "MMBT2222A")
      (footprint "eagle-import:SOT23-3")
      (fields (field (name "PARTNO") "BC817-25,215"))
      (libsource (lib "eagle-import") (part "TRANSISTOR_NPNMMBT2222A"))
    )
    (comp (ref "R2")
      (value "27R")
      (footprint "eagle-import:R1206")
      (fields (field (name "PARTNO") "ERJ-3GEYJ220V"))
      (libsource (lib "eagle-import") (part "resistor_R-EU_R1206"))
    )
    (comp (ref "R3")
      (value "1k")
      (footprint "eagle-import:R0603-DASHES")
      (fields (field (name "PARTNO") "ERJ-3GEYJ102V"))
      (libsource (lib "eagle-import") (part "sha2017_rev0_1_0_dev_R0603-DASHES"))
    )
    (comp (ref "R5")
      (value "10k")
      (footprint "eagle-import:R0603-DASHES")
      (fields (field (name "PARTNO") "ERJ-3GEYJ103V"))
      (libsource (lib "eagle-import") (part "R0603-DASHES"))
    )
    (comp (ref "R8")
      (value "10k")
      (footprint "eagle-import:R0603-DASHES")
      (fields (field (name "PARTNO") "ERJ-3GEYJ103V"))
      (libsource (lib "eagle-import") (part "R0603-DASHES"))
    )
    (comp (ref "R11")
      (value "10k")
      (footprint "eagle-import:R0603-DASHES")
      (fields (field (name "PARTNO") "ERJ-3GEYJ103V"))
      (libsource (lib "eagle-import") (part "R0603-DASHES"))
    )
    (comp (ref "R12")
      (value "1k")
      (footprint "eagle-import:R0603-DASHES")
      (fields (field (name "PARTNO") "ERJ-3GEYJ102V"))
      (libsource (lib "eagle-import") (part "sha2017_rev0_1_0_dev_R0603-DASHES"))
    )
    (comp (ref "R13")
      (value "10k")
      (footprint "eagle-import:R0603-DASHES")
      (fields (field (name "PARTNO") "ERJ-3GEYJ103V"))
      (libsource (lib "eagle-import") (part "sha2017_rev0_1_0_dev_R0603-DASHES"))
    )
    (comp (ref "R14")
      (value "1k")
      (footprint "eagle-import:R0603-DASHES")
      (fields (field (name "PARTNO") "ERJ-3GEYJ102V"))
      (libsource (lib "eagle-import") (part "sha2017_rev0_1_0_dev_R0603-DASHES"))
    )
    (comp (ref "R15")
      (value "10k")
      (footprint "eagle-import:R0603-DASHES")
      (fields (field (name "PARTNO") "ERJ-3GEYJ103V"))
      (libsource (lib "eagle-import") (part "sha2017_rev0_1_0_dev_R0603-DASHES"))
    )
    (comp (ref "R16")
      (value "10k")
      (footprint "eagle-import:R0603-DASHES")
      (fields (field (name "PARTNO") "ERJ-3GEYJ103V"))
      (libsource (lib "eagle-import") (part "sha2017_rev0_1_0_dev_R0603-DASHES"))
    )
    (comp (ref "R17")
      (value "10k")
      (footprint "eagle-import:R0603-DASHES")
      (fields (field (name "PARTNO") "ERJ-3GEYJ103V"))
      (libsource (lib "eagle-import") (part "sha2017_rev0_1_0_dev_R0603-DASHES"))
    )
    (comp (ref "R18")
      (value "10k")
      (footprint "eagle-import:R0603-DASHES")
      (fields (field (name "PARTNO") "ERJ-3GEYJ103V"))
      (libsource (lib "eagle-import") (part "sha2017_rev0_1_0_dev_R0603-DASHES"))
    )
    (comp (ref "R19")
      (value "5R")
      (footprint "eagle-import:R0603-DASHES")
      (fields (field (name "PARTNO") "ERJ-3GEYJ5R1V"))
      (libsource (lib "eagle-import") (part "sha2017_rev0_1_0_dev_R0603-DASHES"))
    )
    (comp (ref "R22")
      (value "10k")
      (footprint "eagle-import:R0603-DASHES")
      (fields (field (name "PARTNO") "ERJ-3GEYJ103V"))
      (libsource (lib "eagle-import") (part "sha2017_rev0_1_0_dev_R0603-DASHES"))
    )
    (comp (ref "R25")
      (value "10k")
      (footprint "eagle-import:R0603-DASHES")
      (fields (field (name "PARTNO") "ERJ-3GEYJ103V"))
      (libsource (lib "eagle-import") (part "sha2017_rev0_1_0_dev_R0603-DASHES"))
    )
    (comp (ref "R27")
      (value "10k")
      (footprint "eagle-import:R0603-DASHES")
      (fields (field (name "PARTNO") "ERJ-3GEYJ103V"))
      (libsource (lib "eagle-import") (part "R0603-DASHES"))
    )
    (comp (ref "R28")
      (value "10k")
      (footprint "eagle-import:R0603-DASHES")
      (fields (field (name "PARTNO") "ERJ-3GEYJ103V"))
      (libsource (lib "eagle-import") (part "R0603-DASHES"))
    )
    (comp (ref "R31")
      (value "100k")
      (footprint "eagle-import:R0603-DASHES")
      (fields (field (name "PARTNO") "ERJ-3GEYJ104V"))
      (libsource (lib "eagle-import") (part "sha2017_rev0_1_0_dev_R0603-DASHES"))
    )
    (comp (ref "S1")
      (value "SWITCH-MOMENTARY-2SMD")
      (footprint "eagle-import:TACTILE-SWITCH-SMD")
      (fields (field (name "PARTNO") "SKQGABE010"))
      (libsource (lib "eagle-import") (part "SWITCH-MOMENTARY-2SMD"))
    )
    (comp (ref "S2")
      (value "SWITCH-MOMENTARY-2SMD")
      (footprint "eagle-import:TACTILE-SWITCH-SMD")
      (fields (field (name "PARTNO") "SKQGABE010"))
      (libsource (lib "eagle-import") (part "SWITCH-MOMENTARY-2SMD"))
    )
    (comp (ref "T3")
      (value "MOSFET-PCHANNEL")
      (footprint "eagle-import:SOT23-3")
      (libsource (lib "eagle-import") (part "MOSFET-PCHANNEL"))
    )
    (comp (ref "TP103")
      (value "TEST-POINT3")
      (footprint "eagle-import:PAD.03X.03")
      (fields (field (name "PARTNO") "NAP"))
      (libsource (lib "eagle-import") (part "TEST-POINT3"))
    )
    (comp (ref "TP104")
      (value "TEST-POINT3")
      (footprint "eagle-import:PAD.03X.03")
      (fields (field (name "PARTNO") "NAP"))
      (libsource (lib "eagle-import") (part "TEST-POINT3"))
    )
    (comp (ref "TP105")
      (value "TEST-POINT3")
      (footprint "eagle-import:PAD.03X.03")
      (fields (field (name "PARTNO") "NAP"))
      (libsource (lib "eagle-import") (part "TEST-POINT3"))
    )
    (comp (ref "TP106")
      (value "TEST-POINT3")
      (footprint "eagle-import:PAD.03X.03")
      (fields (field (name "PARTNO") "NAP"))
      (libsource (lib "eagle-import") (part "TEST-POINT3"))
    )
    (comp (ref "TP107")
      (value "TEST-POINT3")
      (footprint "eagle-import:PAD.03X.03")
      (fields (field (name "PARTNO") "NAP"))
      (libsource (lib "eagle-import") (part "TEST-POINT3"))
    )
    (comp (ref "TP108")
      (value "TEST-POINT3")
      (footprint "eagle-import:PAD.03X.03")
      (fields (field (name "PARTNO") "NAP"))
      (libsource (lib "eagle-import") (part "TEST-POINT3"))
    )
    (comp (ref "TP109")
      (value "TEST-POINT3")
      (footprint "eagle-import:PAD.03X.03")
      (fields (field (name "PARTNO") "NAP"))
      (libsource (lib "eagle-import") (part "TEST-POINT3"))
    )
    (comp (ref "TP111")
      (value "TEST-POINT3")
      (footprint "eagle-import:PAD.03X.03")
      (fields (field (name "PARTNO") "NAP"))
      (libsource (lib "eagle-import") (part "TEST-POINT3"))
    )
    (comp (ref "TP113")
      (value "TEST-POINT3")
      (footprint "eagle-import:PAD.03X.03")
      (fields (field (name "PARTNO") "NAP"))
      (libsource (lib "eagle-import") (part "TEST-POINT3"))
    )
    (comp (ref "TP118")
      (value "TEST-POINT3")
      (footprint "eagle-import:PAD.03X.03")
      (fields (field (name "PARTNO") "NAP"))
      (libsource (lib "eagle-import") (part "TEST-POINT3"))
    )
    (comp (ref "TP123")
      (value "TEST-POINT3")
      (footprint "eagle-import:PAD.03X.03")
      (fields (field (name "PARTNO") "NAP"))
      (libsource (lib "eagle-import") (part "TEST-POINT3"))
    )
    (comp (ref "TP124")
      (value "TEST-POINT3")
      (footprint "eagle-import:PAD.03X.03")
      (fields (field (name "PARTNO") "NAP"))
      (libsource (lib "eagle-import") (part "TEST-POINT3"))
    )
    (comp (ref "TP125")
      (value "TEST-POINT3")
      (footprint "eagle-import:PAD.03X.03")
      (fields (field (name "PARTNO") "NAP"))
      (libsource (lib "eagle-import") (part "TEST-POINT3"))
    )
    (comp (ref "TP126")
      (value "TEST-POINT3")
      (footprint "eagle-import:PAD.03X.03")
      (fields (field (name "PARTNO") "NAP"))
      (libsource (lib "eagle-import") (part "TEST-POINT3"))
    )
    (comp (ref "TP127")
      (value "TEST-POINT3")
      (footprint "eagle-import:PAD.03X.03")
      (fields (field (name "PARTNO") "NAP"))
      (libsource (lib "eagle-import") (part "TEST-POINT3"))
    )
    (comp (ref "TP128")
      (value "TEST-POINT3")
      (footprint "eagle-import:PAD.03X.03")
      (fields (field (name "PARTNO") "NAP"))
      (libsource (lib "eagle-import") (part "TEST-POINT3"))
    )
    (comp (ref "TP130")
      (value "TEST-POINT3")
      (footprint "eagle-import:PAD.03X.03")
      (fields (field (name "PARTNO") "NAP"))
      (libsource (lib "eagle-import") (part "TEST-POINT3"))
    )
    (comp (ref "TP131")
      (value "TEST-POINT3")
      (footprint "eagle-import:PAD.03X.03")
      (fields (field (name "PARTNO") "NAP"))
      (libsource (lib "eagle-import") (part "TEST-POINT3"))
    )
    (comp (ref "TP132")
      (value "TEST-POINT3")
      (footprint "eagle-import:PAD.03X.03")
      (fields (field (name "PARTNO") "NAP"))
      (libsource (lib "eagle-import") (part "TEST-POINT3"))
    )
    (comp (ref "TP139")
      (value "TEST-POINT3")
      (footprint "eagle-import:PAD.03X.03")
      (fields (field (name "PARTNO") "NAP"))
      (libsource (lib "eagle-import") (part "TEST-POINT3"))
    )
    (comp (ref "USB1")
      (value "MOLEX-47346-0001")
      (footprint "eagle-import:MOLEX-47364-0001")
      (fields (field (name "PARTNO") "10118192-0001LF"))
      (libsource (lib "eagle-import") (part "MOLEX-47346-0001"))
    )
    (comp (ref "X1")
      (value "68712414022")
      (footprint "eagle-import:68712414022")
      (libsource (lib "eagle-import") (part "68712414022"))
    )
    (comp (ref "X2")
      (value "2908-05WB-MG")
      (footprint "eagle-import:MICRO-SD-SOCKET-PP")
      (libsource (lib "eagle-import") (part "2908-05WB-MG"))
    )
  )
  (nets
    (net (code "1") (name "+3V3") (class "Default")
      (node (ref "C17") (pin "1") (pinfunction "1_1") (pintype "passive"))
      (node (ref "C20") (pin "1") (pinfunction "1_1") (pintype "passive"))
      (node (ref "C22") (pin "1") (pinfunction "1_1") (pintype "passive"))
      (node (ref "C26") (pin "1") (pinfunction "1_1") (pintype "passive"))
      (node (ref "C27") (pin "1") (pinfunction "1_1") (pintype "passive"))
      (node (ref "C30") (pin "1") (pinfunction "1_1") (pintype "passive"))
      (node (ref "C37") (pin "1") (pinfunction "1_1") (pintype "passive"))
      (node (ref "C39") (pin "1") (pinfunction "1_1") (pintype "passive"))
      (node (ref "C43") (pin "1") (pinfunction "1_1") (pintype "passive"))
      (node (ref "C44") (pin "1") (pinfunction "1_1") (pintype "passive"))
      (node (ref "IC2") (pin "3") (pinfunction "OUT_3") (pintype "passive"))
      (node (ref "IC3") (pin "2") (pinfunction "VCC_2") (pintype "power_in"))
      (node (ref "IC5") (pin "2") (pinfunction "VOUT_2") (pintype "output"))
      (node (ref "L1") (pin "1") (pinfunction "1_1") (pintype "passive"))
      (node (ref "R1") (pin "2") (pinfunction "2_2") (pintype "passive"))
      (node (ref "R16") (pin "2") (pinfunction "2_2") (pintype "passive"))
      (node (ref "R22") (pin "1") (pinfunction "1_1") (pintype "passive"))
      (node (ref "R23") (pin "1") (pinfunction "1_1") (pintype "passive"))
      (node (ref "R24") (pin "1") (pinfunction "1_1") (pintype "passive"))
      (node (ref "R28") (pin "2") (pinfunction "2_2") (pintype "passive"))
      (node (ref "R36") (pin "2") (pinfunction "2_2") (pintype "passive"))
      (node (ref "T3") (pin "2") (pinfunction "S_2") (pintype "passive"))
      (node (ref "TP119") (pin "P$1") (pinfunction "1_P$1") (pintype "bidirectional"))
      (node (ref "U1") (pin "20") (pinfunction "V_DD_20") (pintype "power_in"))
      (node (ref "X1") (pin "10") (pinfunction "10_10") (pintype "passive"))
      (node (ref "X1") (pin "7") (pinfunction "7_7") (pintype "passive"))
      (node (ref "X1") (pin "9") (pinfunction "9_9") (pintype "passive"))
    )
    (net (code "2") (name "+5V") (class "Default")
      (node (ref "C11") (pin "1") (pinfunction "1_1") (pintype "passive"))
      (node (ref "C9") (pin "1") (pinfunction "1_1") (pintype "passive"))
      (node (ref "D1") (pin "C") (pinfunction "C_C") (pintype "passive"))
      (node (ref "D3") (pin "A") (pinfunction "A_A") (pintype "passive"))
      (node (ref "F1") (pin "2") (pinfunction "2_2") (pintype "bidirectional"))
      (node (ref "IC1") (pin "7") (pinfunction "REGIN_7") (pintype "passive"))
      (node (ref "IC1") (pin "8") (pinfunction "VBUS_8") (pintype "input"))
      (node (ref "R30") (pin "1") (pinfunction "1_1") (pintype "passive"))
      (node (ref "R4") (pin "2") (pinfunction "2_2") (pintype "passive"))
      (node (ref "R7") (pin "2") (pinfunction "2_2") (pintype "passive"))
      (node (ref "T1") (pin "1") (pinfunction "G_1") (pintype "passive"))
      (node (ref "TP112") (pin "P$1") (pinfunction "1_P$1") (pintype "bidirectional"))
    )
    (net (code "3") (name "3V3_SWITCHED") (class "Default")
      (node (ref "C12") (pin "1") (pinfunction "1_1") (pintype "passive"))
      (node (ref "C31") (pin "1") (pinfunction "1_1") (pintype "passive"))
      (node (ref "C40") (pin "1") (pinfunction "1_1") (pintype "passive"))
      (node (ref "C41") (pin "1") (pinfunction "1_1") (pintype "passive"))
      (node (ref "C7") (pin "1") (pinfunction "1_1") (pintype "passive"))
      (node (ref "R17") (pin "2") (pinfunction "2_2") (pintype "passive"))
      (node (ref "R25") (pin "2") (pinfunction "2_2") (pintype "passive"))
      (node (ref "R31") (pin "1") (pinfunction "1_1") (pintype "passive"))
      (node (ref "R5") (pin "2") (pinfunction "2_2") (pintype "passive"))
      (node (ref "R8") (pin "2") (pinfunction "2_2") (pintype "passive"))
      (node (ref "T3") (pin "3") (pinfunction "D_3") (pintype "passive"))
      (node (ref "TP116") (pin "P$1") (pinfunction "1_P$1") (pintype "bidirectional"))
      (node (ref "X2") (pin "4") (pinfunction "VCC_4") (pintype "bidirectional"))
      (node (ref "X3") (pin "12") (pinfunction "1_12") (pintype "passive"))
    )
    (net (code "4") (name "CHRG_STAT") (class "Default")
      (node (ref "IC4") (pin "7") (pinfunction "CHRG_7") (pintype "bidirectional"))
      (node (ref "R36") (pin "1") (pinfunction "1_1") (pintype "passive"))
      (node (ref "U1") (pin "17") (pinfunction "ELE9_17") (pintype "output"))
    )
    (net (code "5") (name "ESP32_FLASH") (class "Default")
      (node (ref "D2") (pin "C") (pinfunction "C_C") (pintype "passive"))
      (node (ref "IC3") (pin "25") (pinfunction "IO0_25") (pintype "bidirectional"))
      (node (ref "Q4") (pin "3") (pinfunction "C_3") (pintype "passive"))
      (node (ref "R16") (pin "1") (pinfunction "1_1") (pintype "passive"))
      (node (ref "S2") (pin "3") (pinfunction "2_3") (pintype "passive"))
      (node (ref "TP120") (pin "P$1") (pinfunction "1_P$1") (pintype "bidirectional"))
    )
    (net (code "6") (name "ESP32_RX") (class "Default")
      (node (ref "D4") (pin "C") (pinfunction "C_C") (pintype "passive"))
      (node (ref "IC1") (pin "26") (pinfunction "TXD_26") (pintype "output"))
      (node (ref "IC3") (pin "34") (pinfunction "RXD0_34") (pintype "bidirectional"))
      (node (ref "TP133") (pin "P$1") (pinfunction "1_P$1") (pintype "bidirectional"))
    )
    (net (code "7") (name "ESP32_TX") (class "Default")
      (node (ref "D5") (pin "C") (pinfunction "C_C") (pintype "passive"))
      (node (ref "IC1") (pin "25") (pinfunction "RXD_25") (pintype "input"))
      (node (ref "IC3") (pin "35") (pinfunction "TXD0_35") (pintype "bidirectional"))
      (node (ref "TP134") (pin "P$1") (pinfunction "1_P$1") (pintype "bidirectional"))
    )
    (net (code "8") (name "ESP32_~{RESET}") (class "Default")
      (node (ref "IC3") (pin "3") (pinfunction "EN_3") (pintype "bidirectional"))
      (node (ref "Q3") (pin "3") (pinfunction "C_3") (pintype "passive"))
      (node (ref "R22") (pin "2") (pinfunction "2_2") (pintype "passive"))
      (node (ref "S1") (pin "3") (pinfunction "2_3") (pintype "passive"))
      (node (ref "TP121") (pin "P$1") (pinfunction "1_P$1") (pintype "bidirectional"))
    )
    (net (code "9") (name "EXTIO-0") (class "Default")
      (node (ref "IC3") (pin "9") (pinfunction "IO33_9") (pintype "bidirectional"))
      (node (ref "X3") (pin "3") (pinfunction "10_3") (pintype "passive"))
    )
    (net (code "10") (name "EXTIO-1") (class "Default")
      (node (ref "IC3") (pin "27") (pinfunction "IO16_27") (pintype "bidirectional"))
      (node (ref "X3") (pin "4") (pinfunction "9_4") (pintype "passive"))
    )
    (net (code "11") (name "EXTIO-2") (class "Default")
      (node (ref "IC3") (pin "28") (pinfunction "IO17_28") (pintype "bidirectional"))
      (node (ref "X3") (pin "5") (pinfunction "8_5") (pintype "passive"))
    )
    (net (code "12") (name "EXTIO-3") (class "Default")
      (node (ref "IC3") (pin "26") (pinfunction "IO4_26") (pintype "bidirectional"))
      (node (ref "X3") (pin "9") (pinfunction "4_9") (pintype "passive"))
    )
    (net (code "13") (name "EXTIO-4") (class "Default")
      (node (ref "IC3") (pin "14") (pinfunction "IO12_14") (pintype "bidirectional"))
      (node (ref "X3") (pin "10") (pinfunction "3_10") (pintype "passive"))
    )
    (net (code "14") (name "GDR") (class "Default")
      (node (ref "Q5") (pin "1") (pinfunction "G_1") (pintype "passive"))
      (node (ref "TP124") (pin "P$1") (pinfunction "1_P$1") (pintype "bidirectional"))
      (node (ref "X1") (pin "23") (pinfunction "23_23") (pintype "passive"))
    )
    (net (code "15") (name "GND") (class "Default")
      (node (ref "$$U$1") (pin "P$1") (pinfunction "P$1_P$1") (pintype "bidirectional"))
      (node (ref "$$U$2") (pin "P$1") (pinfunction "P$1_P$1") (pintype "bidirectional"))
      (node (ref "$$U$3") (pin "P$1") (pinfunction "P$1_P$1") (pintype "bidirectional"))
      (node (ref "$$U$4") (pin "P$1") (pinfunction "P$1_P$1") (pintype "bidirectional"))
      (node (ref "$$U$5") (pin "P$1") (pinfunction "P$1_P$1") (pintype "bidirectional"))
      (node (ref "$$U$6") (pin "P$1") (pinfunction "P$1_P$1") (pintype "bidirectional"))
      (node (ref "$$U$7") (pin "P$1") (pinfunction "P$1_P$1") (pintype "bidirectional"))
      (node (ref "$$U$8") (pin "P$1") (pinfunction "P$1_P$1") (pintype "bidirectional"))
      (node (ref "$$U$9") (pin "P$1") (pinfunction "P$1_P$1") (pintype "bidirectional"))
      (node (ref "C1") (pin "1") (pinfunction "1_1") (pintype "passive"))
      (node (ref "C10") (pin "2") (pinfunction "2_2") (pintype "passive"))
      (node (ref "C11") (pin "2") (pinfunction "2_2") (pintype "passive"))
      (node (ref "C12") (pin "2") (pinfunction "2_2") (pintype "passive"))
      (node (ref "C13") (pin "2") (pinfunction "2_2") (pintype "passive"))
      (node (ref "C14") (pin "2") (pinfunction "2_2") (pintype "passive"))
      (node (ref "C15") (pin "2") (pinfunction "2_2") (pintype "passive"))
      (node (ref "C16") (pin "2") (pinfunction "2_2") (pintype "passive"))
      (node (ref "C17") (pin "2") (pinfunction "2_2") (pintype "passive"))
      (node (ref "C18") (pin "2") (pinfunction "2_2") (pintype "passive"))
      (node (ref "C19") (pin "1") (pinfunction "1_1") (pintype "passive"))
      (node (ref "C2") (pin "1") (pinfunction "1_1") (pintype "passive"))
      (node (ref "C20") (pin "2") (pinfunction "2_2") (pintype "passive"))
      (node (ref "C21") (pin "1") (pinfunction "1_1") (pintype "passive"))
      (node (ref "C22") (pin "2") (pinfunction "2_2") (pintype "passive"))
      (node (ref "C23") (pin "1") (pinfunction "1_1") (pintype "passive"))
      (node (ref "C24") (pin "2") (pinfunction "2_2") (pintype "passive"))
      (node (ref "C26") (pin "2") (pinfunction "2_2") (pintype "passive"))
      (node (ref "C27") (pin "2") (pinfunction "2_2") (pintype "passive"))
      (node (ref "C28") (pin "1") (pinfunction "1_1") (pintype "passive"))
      (node (ref "C29") (pin "1") (pinfunction "1_1") (pintype "passive"))
      (node (ref "C3") (pin "1") (pinfunction "1_1") (pintype "passive"))
      (node (ref "C30") (pin "2") (pinfunction "2_2") (pintype "passive"))
      (node (ref "C31") (pin "2") (pinfunction "2_2") (pintype "passive"))
      (node (ref "C32") (pin "1") (pinfunction "1_1") (pintype "passive"))
      (node (ref "C33") (pin "1") (pinfunction "1_1") (pintype "passive"))
      (node (ref "C34") (pin "2") (pinfunction "2_2") (pintype "passive"))
      (node (ref "C35") (pin "1") (pinfunction "1_1") (pintype "passive"))
      (node (ref "C36") (pin "1") (pinfunction "1_1") (pintype "passive"))
      (node (ref "C37") (pin "2") (pinfunction "2_2") (pintype "passive"))
      (node (ref "C38") (pin "1") (pinfunction "1_1") (pintype "passive"))
      (node (ref "C39") (pin "2") (pinfunction "2_2") (pintype "passive"))
      (node (ref "C4") (pin "1") (pinfunction "1_1") (pintype "passive"))
      (node (ref "C40") (pin "2") (pinfunction "2_2") (pintype "passive"))
      (node (ref "C41") (pin "2") (pinfunction "2_2") (pintype "passive"))
      (node (ref "C43") (pin "2") (pinfunction "2_2") (pintype "passive"))
      (node (ref "C44") (pin "2") (pinfunction "2_2") (pintype "passive"))
      (node (ref "C45") (pin "2") (pinfunction "2_2") (pintype "passive"))
      (node (ref "C5") (pin "1") (pinfunction "1_1") (pintype "passive"))
      (node (ref "C6") (pin "1") (pinfunction "1_1") (pintype "passive"))
      (node (ref "C7") (pin "2") (pinfunction "2_2") (pintype "passive"))
      (node (ref "C8") (pin "2") (pinfunction "2_2") (pintype "passive"))
      (node (ref "C9") (pin "2") (pinfunction "2_2") (pintype "passive"))
      (node (ref "D1") (pin "A") (pinfunction "A_A") (pintype "passive"))
      (node (ref "D100") (pin "3") (pinfunction "VSS_3") (pintype "power_in"))
      (node (ref "D101") (pin "3") (pinfunction "VSS_3") (pintype "power_in"))
      (node (ref "D102") (pin "3") (pinfunction "VSS_3") (pintype "power_in"))
      (node (ref "D103") (pin "3") (pinfunction "VSS_3") (pintype "power_in"))
      (node (ref "D104") (pin "3") (pinfunction "VSS_3") (pintype "power_in"))
      (node (ref "D105") (pin "3") (pinfunction "VSS_3") (pintype "power_in"))
      (node (ref "D6") (pin "C") (pinfunction "C_C") (pintype "passive"))
      (node (ref "D7") (pin "C") (pinfunction "C_C") (pintype "passive"))
      (node (ref "IC1") (pin "3") (pinfunction "GND_3") (pintype "power_in"))
      (node (ref "IC1") (pin "EXP") (pinfunction "GND_EXP") (pintype "power_in"))
      (node (ref "IC1") (pin "M") (pinfunction "GND_M") (pintype "power_in"))
      (node (ref "IC2") (pin "1") (pinfunction "GND_1") (pintype "input"))
      (node (ref "IC3") (pin "0") (pinfunction "GND_0") (pintype "power_in"))
      (node (ref "IC3") (pin "1") (pinfunction "GND_1") (pintype "power_in"))
      (node (ref "IC3") (pin "15") (pinfunction "GND_15") (pintype "power_in"))
      (node (ref "IC3") (pin "38") (pinfunction "GND_38") (pintype "power_in"))
      (node (ref "IC4") (pin "3") (pinfunction "GND_3") (pintype "bidirectional"))
      (node (ref "IC5") (pin "1") (pinfunction "GND_1") (pintype "power_in"))
      (node (ref "Q1") (pin "2") (pinfunction "E_2") (pintype "passive"))
      (node (ref "Q2") (pin "2") (pinfunction "E_2") (pintype "passive"))
      (node (ref "Q6") (pin "2") (pinfunction "E_2") (pintype "passive"))
      (node (ref "R19") (pin "2") (pinfunction "2_2") (pintype "passive"))
      (node (ref "R20") (pin "1") (pinfunction "1_1") (pintype "passive"))
      (node (ref "R35") (pin "2") (pinfunction "2_2") (pintype "passive"))
      (node (ref "R37") (pin "1") (pinfunction "1_1") (pintype "passive"))
      (node (ref "R4") (pin "1") (pinfunction "1_1") (pintype "passive"))
      (node (ref "R6") (pin "1") (pinfunction "1_1") (pintype "passive"))
      (node (ref "S1") (pin "1") (pinfunction "1_1") (pintype "passive"))
      (node (ref "S2") (pin "1") (pinfunction "1_1") (pintype "passive"))
      (node (ref "SJ3") (pin "1") (pinfunction "1_1") (pintype "passive"))
      (node (ref "TP1") (pin "P$1") (pinfunction "1_P$1") (pintype "bidirectional"))
      (node (ref "TP102") (pin "P$1") (pinfunction "1_P$1") (pintype "bidirectional"))
      (node (ref "TP103") (pin "P$1") (pinfunction "1_P$1") (pintype "bidirectional"))
      (node (ref "TP106") (pin "P$1") (pinfunction "1_P$1") (pintype "bidirectional"))
      (node (ref "TP122") (pin "P$1") (pinfunction "1_P$1") (pintype "bidirectional"))
      (node (ref "TP125") (pin "P$1") (pinfunction "1_P$1") (pintype "bidirectional"))
      (node (ref "TP135") (pin "P$1") (pinfunction "1_P$1") (pintype "bidirectional"))
      (node (ref "TP140") (pin "P$1") (pinfunction "1_P$1") (pintype "bidirectional"))
      (node (ref "U$10") (pin "P$1") (pinfunction "P$1_P$1") (pintype "bidirectional"))
      (node (ref "U$11") (pin "P$1") (pinfunction "P$1_P$1") (pintype "bidirectional"))
      (node (ref "U$12") (pin "P$1") (pinfunction "P$1_P$1") (pintype "bidirectional"))
      (node (ref "U$13") (pin "P$1") (pinfunction "P$1_P$1") (pintype "bidirectional"))
      (node (ref "U$14") (pin "P$1") (pinfunction "P$1_P$1") (pintype "bidirectional"))
      (node (ref "U$15") (pin "P$1") (pinfunction "P$1_P$1") (pintype "bidirectional"))
      (node (ref "U$16") (pin "P$1") (pinfunction "P$1_P$1") (pintype "bidirectional"))
      (node (ref "U$17") (pin "P$1") (pinfunction "P$1_P$1") (pintype "bidirectional"))
      (node (ref "U$18") (pin "P$1") (pinfunction "P$1_P$1") (pintype "bidirectional"))
      (node (ref "U$19") (pin "P$1") (pinfunction "P$1_P$1") (pintype "bidirectional"))
      (node (ref "U$2") (pin "P$1") (pinfunction "P$1_P$1") (pintype "bidirectional"))
      (node (ref "U$20") (pin "P$1") (pinfunction "P$1_P$1") (pintype "bidirectional"))
      (node (ref "U$21") (pin "P$1") (pinfunction "P$1_P$1") (pintype "bidirectional"))
      (node (ref "U$22") (pin "P$1") (pinfunction "P$1_P$1") (pintype "bidirectional"))
      (node (ref "U$23") (pin "P$1") (pinfunction "P$1_P$1") (pintype "bidirectional"))
      (node (ref "U$3") (pin "P$1") (pinfunction "P$1_P$1") (pintype "bidirectional"))
      (node (ref "U$4") (pin "P$1") (pinfunction "P$1_P$1") (pintype "bidirectional"))
      (node (ref "U$5") (pin "P$1") (pinfunction "P$1_P$1") (pintype "bidirectional"))
      (node (ref "U$6") (pin "P$1") (pinfunction "P$1_P$1") (pintype "bidirectional"))
      (node (ref "U1") (pin "4") (pinfunction "ADDR_4") (pintype "input"))
      (node (ref "U1") (pin "6") (pinfunction "V_SS_6") (pintype "power_in"))
      (node (ref "USB1") (pin "5") (pinfunction "5_5") (pintype "input"))
      (node (ref "USB1") (pin "GND1") (pinfunction "GND1_GND1") (pintype "bidirectional"))
      (node (ref "USB1") (pin "GND2") (pinfunction "GND2_GND2") (pintype "bidirectional"))
      (node (ref "USB1") (pin "GND3") (pinfunction "GND3_GND3") (pintype "bidirectional"))
      (node (ref "USB1") (pin "GND4") (pinfunction "GND4_GND4") (pintype "bidirectional"))
      (node (ref "X1") (pin "17") (pinfunction "17_17") (pintype "passive"))
      (node (ref "X1") (pin "8") (pinfunction "8_8") (pintype "passive"))
      (node (ref "X2") (pin "6") (pinfunction "GND_6") (pintype "bidirectional"))
      (node (ref "X2") (pin "CD2") (pinfunction "SHIELD_CD2") (pintype "bidirectional"))
      (node (ref "X2") (pin "GND1") (pinfunction "SHIELD_GND1") (pintype "bidirectional"))
      (node (ref "X2") (pin "GND3") (pinfunction "SHIELD_GND3") (pintype "bidirectional"))
      (node (ref "X3") (pin "1") (pinfunction "12_1") (pintype "passive"))
      (node (ref "X3") (pin "11") (pinfunction "2_11") (pintype "passive"))
      (node (ref "X4") (pin "2") (pinfunction "1_2") (pintype "passive"))
    )
    (net (code "16") (name "I2C_INT") (class "Default")
      (node (ref "IC3") (pin "10") (pinfunction "IO25_10") (pintype "bidirectional"))
      (node (ref "R1") (pin "1") (pinfunction "1_1") (pintype "passive"))
      (node (ref "U1") (pin "1") (pinfunction "~{IRQ}_1") (pintype "input"))
    )
    (net (code "17") (name "I2C_SCL") (class "Default")
      (node (ref "IC3") (pin "12") (pinfunction "IO27_12") (pintype "bidirectional"))
      (node (ref "R24") (pin "2") (pinfunction "2_2") (pintype "passive"))
      (node (ref "TP100") (pin "P$1") (pinfunction "1_P$1") (pintype "bidirectional"))
      (node (ref "TP114") (pin "P$1") (pinfunction "1_P$1") (pintype "bidirectional"))
      (node (ref "TP3") (pin "P$1") (pinfunction "1_P$1") (pintype "bidirectional"))
      (node (ref "U1") (pin "2") (pinfunction "SCL_2") (pintype "input"))
      (node (ref "X3") (pin "6") (pinfunction "7_6") (pintype "passive"))
    )
    (net (code "18") (name "I2C_SDA") (class "Default")
      (node (ref "IC3") (pin "11") (pinfunction "IO26_11") (pintype "bidirectional"))
      (node (ref "R23") (pin "2") (pinfunction "2_2") (pintype "passive"))
      (node (ref "TP101") (pin "P$1") (pinfunction "1_P$1") (pintype "bidirectional"))
      (node (ref "TP115") (pin "P$1") (pinfunction "1_P$1") (pintype "bidirectional"))
      (node (ref "TP2") (pin "P$1") (pinfunction "1_P$1") (pintype "bidirectional"))
      (node (ref "U1") (pin "3") (pinfunction "SDA_3") (pintype "input"))
      (node (ref "X3") (pin "7") (pinfunction "6_7") (pintype "passive"))
    )
    (net (code "19") (name "LCD_BUSY") (class "Default")
      (node (ref "IC3") (pin "36") (pinfunction "IO22_36") (pintype "bidirectional"))
      (node (ref "TP118") (pin "P$1") (pinfunction "1_P$1") (pintype "bidirectional"))
      (node (ref "X1") (pin "16") (pinfunction "16_16") (pintype "passive"))
    )
    (net (code "20") (name "LCD_CS") (class "Default")
      (node (ref "IC3") (pin "31") (pinfunction "IO19_31") (pintype "bidirectional"))
      (node (ref "TP109") (pin "P$1") (pinfunction "1_P$1") (pintype "bidirectional"))
      (node (ref "X1") (pin "13") (pinfunction "13_13") (pintype "passive"))
    )
    (net (code "21") (name "LCD_D{slash}~{S}") (class "Default")
      (node (ref "IC3") (pin "33") (pinfunction "IO21_33") (pintype "bidirectional"))
      (node (ref "TP111") (pin "P$1") (pinfunction "1_P$1") (pintype "bidirectional"))
      (node (ref "X1") (pin "14") (pinfunction "14_14") (pintype "passive"))
    )
    (net (code "22") (name "LCD_MOSI") (class "Default")
      (node (ref "IC3") (pin "29") (pinfunction "IO5_29") (pintype "bidirectional"))
      (node (ref "TP107") (pin "P$1") (pinfunction "1_P$1") (pintype "bidirectional"))
      (node (ref "X1") (pin "11") (pinfunction "11_11") (pintype "passive"))
    )
    (net (code "23") (name "LCD_SCK") (class "Default")
      (node (ref "IC3") (pin "30") (pinfunction "IO18_30") (pintype "bidirectional"))
      (node (ref "TP108") (pin "P$1") (pinfunction "1_P$1") (pintype "bidirectional"))
      (node (ref "X1") (pin "12") (pinfunction "12_12") (pintype "passive"))
    )
    (net (code "24") (name "LCD_~{RESET}") (class "Default")
      (node (ref "IC3") (pin "37") (pinfunction "IO23_37") (pintype "bidirectional"))
      (node (ref "TP113") (pin "P$1") (pinfunction "1_P$1") (pintype "bidirectional"))
      (node (ref "X1") (pin "15") (pinfunction "15_15") (pintype "passive"))
    )
    (net (code "25") (name "Net-(C25-Pad1)") (class "Default")
      (node (ref "C25") (pin "1") (pinfunction "1_1") (pintype "passive"))
      (node (ref "D7") (pin "A") (pinfunction "A_A") (pintype "passive"))
      (node (ref "D8") (pin "C") (pinfunction "C_C") (pintype "passive"))
    )
    (net (code "26") (name "Net-(D4-PadA)") (class "Default")
      (node (ref "D4") (pin "A") (pinfunction "A_A") (pintype "passive"))
      (node (ref "R3") (pin "1") (pinfunction "1_1") (pintype "passive"))
    )
    (net (code "27") (name "Net-(D5-PadA)") (class "Default")
      (node (ref "D5") (pin "A") (pinfunction "A_A") (pintype "passive"))
      (node (ref "R14") (pin "1") (pinfunction "1_1") (pintype "passive"))
    )
    (net (code "28") (name "Net-(D6-PadA)") (class "Default")
      (node (ref "D6") (pin "A") (pinfunction "A_A") (pintype "passive"))
      (node (ref "R12") (pin "1") (pinfunction "1_1") (pintype "passive"))
    )
    (net (code "29") (name "Net-(D100-DIN)") (class "Default")
      (node (ref "D100") (pin "4") (pinfunction "DIN_4") (pintype "input"))
      (node (ref "D101") (pin "2") (pinfunction "DOUT_2") (pintype "output"))
    )
    (net (code "30") (name "Net-(D101-DIN)") (class "Default")
      (node (ref "D101") (pin "4") (pinfunction "DIN_4") (pintype "input"))
      (node (ref "D102") (pin "2") (pinfunction "DOUT_2") (pintype "output"))
    )
    (net (code "31") (name "Net-(D102-DIN)") (class "Default")
      (node (ref "D102") (pin "4") (pinfunction "DIN_4") (pintype "input"))
      (node (ref "D103") (pin "2") (pinfunction "DOUT_2") (pintype "output"))
    )
    (net (code "32") (name "Net-(D103-DIN)") (class "Default")
      (node (ref "D103") (pin "4") (pinfunction "DIN_4") (pintype "input"))
      (node (ref "D104") (pin "2") (pinfunction "DOUT_2") (pintype "output"))
    )
    (net (code "33") (name "Net-(D104-DIN)") (class "Default")
      (node (ref "D104") (pin "4") (pinfunction "DIN_4") (pintype "input"))
      (node (ref "D105") (pin "2") (pinfunction "DOUT_2") (pintype "output"))
    )
    (net (code "34") (name "Net-(IC1-DTR)") (class "Default")
      (node (ref "IC1") (pin "28") (pinfunction "DTR_28") (pintype "output"))
      (node (ref "Q4") (pin "2") (pinfunction "E_2") (pintype "passive"))
      (node (ref "R18") (pin "1") (pinfunction "1_1") (pintype "passive"))
    )
    (net (code "35") (name "Net-(IC1-RTS)") (class "Default")
      (node (ref "IC1") (pin "24") (pinfunction "RTS_24") (pintype "output"))
      (node (ref "Q3") (pin "2") (pinfunction "E_2") (pintype "passive"))
      (node (ref "R15") (pin "1") (pinfunction "1_1") (pintype "passive"))
    )
    (net (code "36") (name "Net-(IC1-~{RST})") (class "Default")
      (node (ref "IC1") (pin "9") (pinfunction "~{RST}_9") (pintype "bidirectional"))
      (node (ref "R13") (pin "2") (pinfunction "2_2") (pintype "passive"))
    )
    (net (code "37") (name "Net-(IC3-CLK)") (class "Default")
      (node (ref "IC3") (pin "20") (pinfunction "CLK_20") (pintype "bidirectional"))
      (node (ref "TP130") (pin "P$1") (pinfunction "1_P$1") (pintype "bidirectional"))
    )
    (net (code "38") (name "Net-(IC3-CND)") (class "Default")
      (node (ref "IC3") (pin "19") (pinfunction "CND_19") (pintype "bidirectional"))
      (node (ref "TP128") (pin "P$1") (pinfunction "1_P$1") (pintype "bidirectional"))
    )
    (net (code "39") (name "Net-(IC3-SD0)") (class "Default")
      (node (ref "IC3") (pin "21") (pinfunction "SD0_21") (pintype "bidirectional"))
      (node (ref "TP131") (pin "P$1") (pinfunction "1_P$1") (pintype "bidirectional"))
    )
    (net (code "40") (name "Net-(IC3-SD1)") (class "Default")
      (node (ref "IC3") (pin "22") (pinfunction "SD1_22") (pintype "bidirectional"))
      (node (ref "TP132") (pin "P$1") (pinfunction "1_P$1") (pintype "bidirectional"))
    )
    (net (code "41") (name "Net-(IC3-SD2)") (class "Default")
      (node (ref "IC3") (pin "17") (pinfunction "SD2_17") (pintype "bidirectional"))
      (node (ref "TP126") (pin "P$1") (pinfunction "1_P$1") (pintype "bidirectional"))
    )
    (net (code "42") (name "Net-(IC3-SD3)") (class "Default")
      (node (ref "IC3") (pin "18") (pinfunction "SD3_18") (pintype "bidirectional"))
      (node (ref "TP127") (pin "P$1") (pinfunction "1_P$1") (pintype "bidirectional"))
    )
    (net (code "43") (name "Net-(IC3-SENSOR_VN)") (class "Default")
      (node (ref "C29") (pin "2") (pinfunction "2_2") (pintype "passive"))
      (node (ref "IC3") (pin "5") (pinfunction "SENSOR_VN_5") (pintype "bidirectional"))
    )
    (net (code "44") (name "Net-(IC3-SENSOR_VP)") (class "Default")
      (node (ref "C28") (pin "2") (pinfunction "2_2") (pintype "passive"))
      (node (ref "IC3") (pin "4") (pinfunction "SENSOR_VP_4") (pintype "bidirectional"))
    )
    (net (code "45") (name "Net-(IC4-BAT)") (class "Default")
      (node (ref "C34") (pin "1") (pinfunction "1_1") (pintype "passive"))
      (node (ref "F2") (pin "1") (pinfunction "1_1") (pintype "bidirectional"))
      (node (ref "IC4") (pin "5") (pinfunction "BAT_5") (pintype "bidirectional"))
      (node (ref "X4") (pin "3") (pinfunction "1_3") (pintype "passive"))
    )
    (net (code "46") (name "Net-(IC4-CE)") (class "Default")
      (node (ref "C23") (pin "2") (pinfunction "2_2") (pintype "passive"))
      (node (ref "C24") (pin "1") (pinfunction "1_1") (pintype "passive"))
      (node (ref "IC4") (pin "4") (pinfunction "VCC_4") (pintype "bidirectional"))
      (node (ref "IC4") (pin "8") (pinfunction "CE_8") (pintype "bidirectional"))
      (node (ref "R30") (pin "2") (pinfunction "2_2") (pintype "passive"))
      (node (ref "R32") (pin "2") (pinfunction "2_2") (pintype "passive"))
    )
    (net (code "47") (name "Net-(IC4-PROG)") (class "Default")
      (node (ref "IC4") (pin "2") (pinfunction "PROG_2") (pintype "bidirectional"))
      (node (ref "R29") (pin "1") (pinfunction "1_1") (pintype "passive"))
    )
    (net (code "48") (name "Net-(M1-Pad+)") (class "Default")
      (node (ref "M1") (pin "+") (pinfunction "+_+") (pintype "bidirectional"))
      (node (ref "R2") (pin "1") (pinfunction "1_1") (pintype "passive"))
    )
    (net (code "49") (name "Net-(Q1-B)") (class "Default")
      (node (ref "Q1") (pin "1") (pinfunction "B_1") (pintype "passive"))
      (node (ref "R10") (pin "2") (pinfunction "2_2") (pintype "passive"))
    )
    (net (code "50") (name "Net-(Q1-C)") (class "Default")
      (node (ref "Q1") (pin "3") (pinfunction "C_3") (pintype "passive"))
      (node (ref "R9") (pin "1") (pinfunction "1_1") (pintype "passive"))
      (node (ref "T2") (pin "1") (pinfunction "G_1") (pintype "passive"))
    )
    (net (code "51") (name "Net-(Q2-B)") (class "Default")
      (node (ref "Q2") (pin "1") (pinfunction "B_1") (pintype "passive"))
      (node (ref "R11") (pin "1") (pinfunction "1_1") (pintype "passive"))
    )
    (net (code "52") (name "Net-(Q2-C)") (class "Default")
      (node (ref "M1") (pin "-") (pinfunction "-_-") (pintype "bidirectional"))
      (node (ref "Q2") (pin "3") (pinfunction "C_3") (pintype "passive"))
    )
    (net (code "53") (name "Net-(Q3-B)") (class "Default")
      (node (ref "Q3") (pin "1") (pinfunction "B_1") (pintype "passive"))
      (node (ref "R18") (pin "2") (pinfunction "2_2") (pintype "passive"))
    )
    (net (code "54") (name "Net-(Q4-B)") (class "Default")
      (node (ref "Q4") (pin "1") (pinfunction "B_1") (pintype "passive"))
      (node (ref "R15") (pin "2") (pinfunction "2_2") (pintype "passive"))
    )
    (net (code "55") (name "Net-(Q5-D)") (class "Default")
      (node (ref "C25") (pin "2") (pinfunction "2_2") (pintype "passive"))
      (node (ref "D9") (pin "A") (pinfunction "A_A") (pintype "passive"))
      (node (ref "L1") (pin "2") (pinfunction "2_2") (pintype "passive"))
      (node (ref "Q5") (pin "3") (pinfunction "D_3") (pintype "passive"))
    )
    (net (code "56") (name "Net-(Q6-B)") (class "Default")
      (node (ref "Q6") (pin "1") (pinfunction "B_1") (pintype "passive"))
      (node (ref "R27") (pin "2") (pinfunction "2_2") (pintype "passive"))
    )
    (net (code "57") (name "Net-(Q6-C)") (class "Default")
      (node (ref "Q6") (pin "3") (pinfunction "C_3") (pintype "passive"))
      (node (ref "R28") (pin "1") (pinfunction "1_1") (pintype "passive"))
      (node (ref "T3") (pin "1") (pinfunction "G_1") (pintype "passive"))
    )
    (net (code "58") (name "Net-(R29-Pad2)") (class "Default")
      (node (ref "R29") (pin "2") (pinfunction "2_2") (pintype "passive"))
      (node (ref "R35") (pin "1") (pinfunction "1_1") (pintype "passive"))
      (node (ref "SJ3") (pin "2") (pinfunction "2_2") (pintype "passive"))
    )
    (net (code "59") (name "Net-(TOUCH_SEL-DOWN)") (class "Default")
      (node (ref "TOUCH_SEL") (pin "D") (pinfunction "DOWN_D") (pintype "bidirectional"))
      (node (ref "U1") (pin "12") (pinfunction "ELE4_12") (pintype "output"))
    )
    (net (code "60") (name "Net-(TOUCH_SEL-LEFT)") (class "Default")
      (node (ref "TOUCH_SEL") (pin "L") (pinfunction "LEFT_L") (pintype "bidirectional"))
      (node (ref "U1") (pin "15") (pinfunction "ELE7_15") (pintype "output"))
    )
    (net (code "61") (name "Net-(TOUCH_SEL-RIGHT)") (class "Default")
      (node (ref "TOUCH_SEL") (pin "R") (pinfunction "RIGHT_R") (pintype "bidirectional"))
      (node (ref "U1") (pin "13") (pinfunction "ELE5_13") (pintype "output"))
    )
    (net (code "62") (name "Net-(TP139-1)") (class "Default")
      (node (ref "F1") (pin "1") (pinfunction "1_1") (pintype "bidirectional"))
      (node (ref "TP139") (pin "P$1") (pinfunction "1_P$1") (pintype "bidirectional"))
      (node (ref "USB1") (pin "1") (pinfunction "1_1") (pintype "input"))
    )
    (net (code "63") (name "Net-(U1-ELE0)") (class "Default")
      (node (ref "TOUCH_A") (pin "P$1") (pinfunction "P$1_P$1") (pintype "bidirectional"))
      (node (ref "U1") (pin "8") (pinfunction "ELE0_8") (pintype "output"))
    )
    (net (code "64") (name "Net-(U1-ELE1)") (class "Default")
      (node (ref "TOUCH_B") (pin "P$1") (pinfunction "P$1_P$1") (pintype "bidirectional"))
      (node (ref "U1") (pin "9") (pinfunction "ELE1_9") (pintype "output"))
    )
    (net (code "65") (name "Net-(U1-ELE2)") (class "Default")
      (node (ref "TOUCH_START") (pin "P$1") (pinfunction "P$1_P$1") (pintype "bidirectional"))
      (node (ref "U1") (pin "10") (pinfunction "ELE2_10") (pintype "output"))
    )
    (net (code "66") (name "Net-(U1-ELE3)") (class "Default")
      (node (ref "TOUCH_SELECT") (pin "P$1") (pinfunction "P$1_P$1") (pintype "bidirectional"))
      (node (ref "U1") (pin "11") (pinfunction "ELE3_11") (pintype "output"))
    )
    (net (code "67") (name "Net-(U1-ELE6)") (class "Default")
      (node (ref "TOUCH_SEL") (pin "UP") (pinfunction "UP_UP") (pintype "bidirectional"))
      (node (ref "U1") (pin "14") (pinfunction "ELE6_14") (pintype "output"))
    )
    (net (code "68") (name "Net-(U1-REXT)") (class "Default")
      (node (ref "R37") (pin "2") (pinfunction "2_2") (pintype "passive"))
      (node (ref "U1") (pin "7") (pinfunction "REXT_7") (pintype "input"))
    )
    (net (code "69") (name "Net-(U1-V_REG)") (class "Default")
      (node (ref "C45") (pin "1") (pinfunction "1_1") (pintype "passive"))
      (node (ref "U1") (pin "5") (pinfunction "V_REG_5") (pintype "input"))
    )
    (net (code "70") (name "PREVGH") (class "Default")
      (node (ref "C32") (pin "2") (pinfunction "2_2") (pintype "passive"))
      (node (ref "D9") (pin "C") (pinfunction "C_C") (pintype "passive"))
      (node (ref "TP104") (pin "P$1") (pinfunction "1_P$1") (pintype "bidirectional"))
      (node (ref "X1") (pin "4") (pinfunction "4_4") (pintype "passive"))
    )
    (net (code "71") (name "PREVGL") (class "Default")
      (node (ref "C36") (pin "2") (pinfunction "2_2") (pintype "passive"))
      (node (ref "D8") (pin "A") (pinfunction "A_A") (pintype "passive"))
      (node (ref "TP105") (pin "P$1") (pinfunction "1_P$1") (pintype "bidirectional"))
      (node (ref "X1") (pin "2") (pinfunction "2_2") (pintype "passive"))
    )
    (net (code "72") (name "RESE") (class "Default")
      (node (ref "Q5") (pin "2") (pinfunction "S_2") (pintype "passive"))
      (node (ref "R19") (pin "1") (pinfunction "1_1") (pintype "passive"))
      (node (ref "TP123") (pin "P$1") (pinfunction "1_P$1") (pintype "bidirectional"))
      (node (ref "X1") (pin "22") (pinfunction "22_22") (pintype "passive"))
    )
    (net (code "73") (name "SD_CD") (class "Default")
      (node (ref "R31") (pin "2") (pinfunction "2_2") (pintype "passive"))
      (node (ref "U1") (pin "19") (pinfunction "ELE11_19") (pintype "output"))
      (node (ref "X2") (pin "CD1") (pinfunction "SHIELD_CD1") (pintype "bidirectional"))
    )
    (net (code "74") (name "SD_CLK") (class "Default")
      (node (ref "IC3") (pin "13") (pinfunction "IO14_13") (pintype "bidirectional"))
      (node (ref "R25") (pin "1") (pinfunction "1_1") (pintype "passive"))
      (node (ref "X2") (pin "5") (pinfunction "SCK_5") (pintype "bidirectional"))
    )
    (net (code "75") (name "SD_CMD") (class "Default")
      (node (ref "IC3") (pin "23") (pinfunction "IO15_23") (pintype "bidirectional"))
      (node (ref "R8") (pin "1") (pinfunction "1_1") (pintype "passive"))
      (node (ref "X2") (pin "3") (pinfunction "DI_3") (pintype "bidirectional"))
    )
    (net (code "76") (name "SD_DATA0") (class "Default")
      (node (ref "D2") (pin "A") (pinfunction "A_A") (pintype "passive"))
      (node (ref "IC3") (pin "24") (pinfunction "IO2_24") (pintype "bidirectional"))
      (node (ref "R5") (pin "1") (pinfunction "1_1") (pintype "passive"))
      (node (ref "X2") (pin "7") (pinfunction "DO_7") (pintype "bidirectional"))
    )
    (net (code "77") (name "SD_DATA3") (class "Default")
      (node (ref "IC3") (pin "16") (pinfunction "IO13_16") (pintype "bidirectional"))
      (node (ref "R17") (pin "1") (pinfunction "1_1") (pintype "passive"))
      (node (ref "X2") (pin "2") (pinfunction "CS_2") (pintype "bidirectional"))
    )
    (net (code "78") (name "TEMP") (class "Default")
      (node (ref "IC4") (pin "1") (pinfunction "TEMP_1") (pintype "bidirectional"))
      (node (ref "R32") (pin "1") (pinfunction "1_1") (pintype "passive"))
      (node (ref "X4") (pin "1") (pinfunction "1_1") (pintype "passive"))
    )
    (net (code "79") (name "TSCL") (class "Default")
      (node (ref "X1") (pin "19") (pinfunction "19_19") (pintype "passive"))
    )
    (net (code "80") (name "TSDA") (class "Default")
      (node (ref "X1") (pin "18") (pinfunction "18_18") (pintype "passive"))
    )
    (net (code "81") (name "USB_DN_CON") (class "Default")
      (node (ref "IC1") (pin "5") (pinfunction "D-_5") (pintype "bidirectional"))
      (node (ref "TP137") (pin "P$1") (pinfunction "1_P$1") (pintype "bidirectional"))
      (node (ref "USB1") (pin "2") (pinfunction "2_2") (pintype "input"))
    )
    (net (code "82") (name "USB_DP_CON") (class "Default")
      (node (ref "IC1") (pin "4") (pinfunction "D+_4") (pintype "bidirectional"))
      (node (ref "TP138") (pin "P$1") (pinfunction "1_P$1") (pintype "bidirectional"))
      (node (ref "USB1") (pin "3") (pinfunction "3_3") (pintype "input"))
    )
    (net (code "83") (name "VBAT") (class "Default")
      (node (ref "F2") (pin "2") (pinfunction "2_2") (pintype "bidirectional"))
      (node (ref "R21") (pin "2") (pinfunction "2_2") (pintype "passive"))
      (node (ref "T1") (pin "3") (pinfunction "D_3") (pintype "passive"))
      (node (ref "TP110") (pin "P$1") (pinfunction "1_P$1") (pintype "bidirectional"))
    )
    (net (code "84") (name "VBAT_SENSE") (class "Default")
      (node (ref "C16") (pin "1") (pinfunction "1_1") (pintype "passive"))
      (node (ref "IC3") (pin "7") (pinfunction "IO35_7") (pintype "bidirectional"))
      (node (ref "R20") (pin "2") (pinfunction "2_2") (pintype "passive"))
      (node (ref "R21") (pin "1") (pinfunction "1_1") (pintype "passive"))
    )
    (net (code "85") (name "VCC") (class "Default")
      (node (ref "C14") (pin "1") (pinfunction "1_1") (pintype "passive"))
      (node (ref "C15") (pin "1") (pinfunction "1_1") (pintype "passive"))
      (node (ref "C18") (pin "1") (pinfunction "1_1") (pintype "passive"))
      (node (ref "D3") (pin "C") (pinfunction "C_C") (pintype "passive"))
      (node (ref "IC2") (pin "2") (pinfunction "IN_2") (pintype "input"))
      (node (ref "IC2") (pin "2@") (pinfunction "IN_2@") (pintype "input"))
      (node (ref "IC5") (pin "3") (pinfunction "VIN_3") (pintype "input"))
      (node (ref "R2") (pin "2") (pinfunction "2_2") (pintype "passive"))
      (node (ref "R9") (pin "2") (pinfunction "2_2") (pintype "passive"))
      (node (ref "T1") (pin "2") (pinfunction "S_2") (pintype "passive"))
      (node (ref "T2") (pin "2") (pinfunction "S_2") (pintype "passive"))
      (node (ref "TP129") (pin "P$1") (pinfunction "1_P$1") (pintype "bidirectional"))
    )
    (net (code "86") (name "VCOM") (class "Default")
      (node (ref "C38") (pin "2") (pinfunction "2_2") (pintype "passive"))
      (node (ref "X1") (pin "1") (pinfunction "1_1") (pintype "passive"))
    )
    (net (code "87") (name "VDD") (class "Default")
      (node (ref "C8") (pin "1") (pinfunction "1_1") (pintype "passive"))
      (node (ref "IC1") (pin "6") (pinfunction "VDD_6") (pintype "power_in"))
      (node (ref "R12") (pin "2") (pinfunction "2_2") (pintype "passive"))
      (node (ref "R13") (pin "1") (pinfunction "1_1") (pintype "passive"))
      (node (ref "R14") (pin "2") (pinfunction "2_2") (pintype "passive"))
      (node (ref "R3") (pin "2") (pinfunction "2_2") (pintype "passive"))
    )
    (net (code "88") (name "VGH") (class "Default")
      (node (ref "C21") (pin "2") (pinfunction "2_2") (pintype "passive"))
      (node (ref "X1") (pin "20") (pinfunction "20_20") (pintype "passive"))
    )
    (net (code "89") (name "VGL") (class "Default")
      (node (ref "C19") (pin "2") (pinfunction "2_2") (pintype "passive"))
      (node (ref "X1") (pin "21") (pinfunction "21_21") (pintype "passive"))
    )
    (net (code "90") (name "VIBRATOR") (class "Default")
      (node (ref "R11") (pin "2") (pinfunction "2_2") (pintype "passive"))
      (node (ref "U1") (pin "16") (pinfunction "ELE8_16") (pintype "output"))
    )
    (net (code "91") (name "VPP") (class "Default")
      (node (ref "X1") (pin "6") (pinfunction "6_6") (pintype "passive"))
    )
    (net (code "92") (name "VSH") (class "Default")
      (node (ref "C33") (pin "2") (pinfunction "2_2") (pintype "passive"))
      (node (ref "X1") (pin "5") (pinfunction "5_5") (pintype "passive"))
    )
    (net (code "93") (name "VSL") (class "Default")
      (node (ref "C35") (pin "2") (pinfunction "2_2") (pintype "passive"))
      (node (ref "X1") (pin "3") (pinfunction "3_3") (pintype "passive"))
    )
    (net (code "94") (name "VUSB_SENSE") (class "Default")
      (node (ref "C10") (pin "1") (pinfunction "1_1") (pintype "passive"))
      (node (ref "IC3") (pin "6") (pinfunction "IO34_6") (pintype "bidirectional"))
      (node (ref "R6") (pin "2") (pinfunction "2_2") (pintype "passive"))
      (node (ref "R7") (pin "1") (pinfunction "1_1") (pintype "passive"))
    )
    (net (code "95") (name "WS2812_DATA") (class "Default")
      (node (ref "D105") (pin "4") (pinfunction "DIN_4") (pintype "input"))
      (node (ref "IC3") (pin "8") (pinfunction "IO32_8") (pintype "bidirectional"))
      (node (ref "TP136") (pin "P$1") (pinfunction "1_P$1") (pintype "bidirectional"))
    )
    (net (code "96") (name "WS2812_DATA_OUT") (class "Default")
      (node (ref "D100") (pin "2") (pinfunction "DOUT_2") (pintype "output"))
      (node (ref "X3") (pin "8") (pinfunction "5_8") (pintype "passive"))
    )
    (net (code "97") (name "WS2812_POWER") (class "Default")
      (node (ref "C1") (pin "2") (pinfunction "2_2") (pintype "passive"))
      (node (ref "C13") (pin "1") (pinfunction "1_1") (pintype "passive"))
      (node (ref "C2") (pin "2") (pinfunction "2_2") (pintype "passive"))
      (node (ref "C3") (pin "2") (pinfunction "2_2") (pintype "passive"))
      (node (ref "C4") (pin "2") (pinfunction "2_2") (pintype "passive"))
      (node (ref "C5") (pin "2") (pinfunction "2_2") (pintype "passive"))
      (node (ref "C6") (pin "2") (pinfunction "2_2") (pintype "passive"))
      (node (ref "D100") (pin "1") (pinfunction "VDD_1") (pintype "power_in"))
      (node (ref "D101") (pin "1") (pinfunction "VDD_1") (pintype "power_in"))
      (node (ref "D102") (pin "1") (pinfunction "VDD_1") (pintype "power_in"))
      (node (ref "D103") (pin "1") (pinfunction "VDD_1") (pintype "power_in"))
      (node (ref "D104") (pin "1") (pinfunction "VDD_1") (pintype "power_in"))
      (node (ref "D105") (pin "1") (pinfunction "VDD_1") (pintype "power_in"))
      (node (ref "T2") (pin "3") (pinfunction "D_3") (pintype "passive"))
      (node (ref "TP117") (pin "P$1") (pinfunction "1_P$1") (pintype "bidirectional"))
      (node (ref "X3") (pin "2") (pinfunction "11_2") (pintype "passive"))
    )
    (net (code "98") (name "WS2812_POWER_EN") (class "Default")
      (node (ref "R10") (pin "1") (pinfunction "1_1") (pintype "passive"))
      (node (ref "R27") (pin "1") (pinfunction "1_1") (pintype "passive"))
      (node (ref "U1") (pin "18") (pinfunction "ELE10_18") (pintype "output"))
    )
    (net (code "99") (name "unconnected-(IC1-CTS-Pad23)") (class "Default")
      (node (ref "IC1") (pin "23") (pinfunction "CTS_23") (pintype "input"))
    )
    (net (code "100") (name "unconnected-(IC1-DCD-Pad1)") (class "Default")
      (node (ref "IC1") (pin "1") (pinfunction "DCD_1") (pintype "input"))
    )
    (net (code "101") (name "unconnected-(IC1-DSR-Pad27)") (class "Default")
      (node (ref "IC1") (pin "27") (pinfunction "DSR_27") (pintype "input"))
    )
    (net (code "102") (name "unconnected-(IC1-RI-Pad2)") (class "Default")
      (node (ref "IC1") (pin "2") (pinfunction "RI_2") (pintype "input"))
    )
    (net (code "103") (name "unconnected-(IC1-SUSPEND-Pad12)") (class "Default")
      (node (ref "IC1") (pin "12") (pinfunction "SUSPEND_12") (pintype "output"))
    )
    (net (code "104") (name "unconnected-(IC1-~{SUSPEND}-Pad11)") (class "Default")
      (node (ref "IC1") (pin "11") (pinfunction "~{SUSPEND}_11") (pintype "output"))
    )
    (net (code "105") (name "unconnected-(IC3-IO20-Pad32)") (class "Default")
      (node (ref "IC3") (pin "32") (pinfunction "IO20_32") (pintype "bidirectional"))
    )
    (net (code "106") (name "unconnected-(IC4-STDBY-Pad6)") (class "Default")
      (node (ref "IC4") (pin "6") (pinfunction "STDBY_6") (pintype "bidirectional"))
    )
    (net (code "107") (name "unconnected-(USB1-Pad4)") (class "Default")
      (node (ref "USB1") (pin "4") (pinfunction "4_4") (pintype "input"))
    )
    (net (code "108") (name "unconnected-(X1-Pad24)") (class "Default")
      (node (ref "X1") (pin "24") (pinfunction "24_24") (pintype "passive"))
    )
    (net (code "109") (name "unconnected-(X2-NC-Pad1)") (class "Default")
      (node (ref "X2") (pin "1") (pinfunction "NC_1") (pintype "bidirectional"))
    )
    (net (code "110") (name "unconnected-(X2-RSV-Pad8)") (class "Default")
      (node (ref "X2") (pin "8") (pinfunction "RSV_8") (pintype "bidirectional"))
    )
  )
)
